# untitled.net
KiCad netlist of a schematic drawn in EAGLE
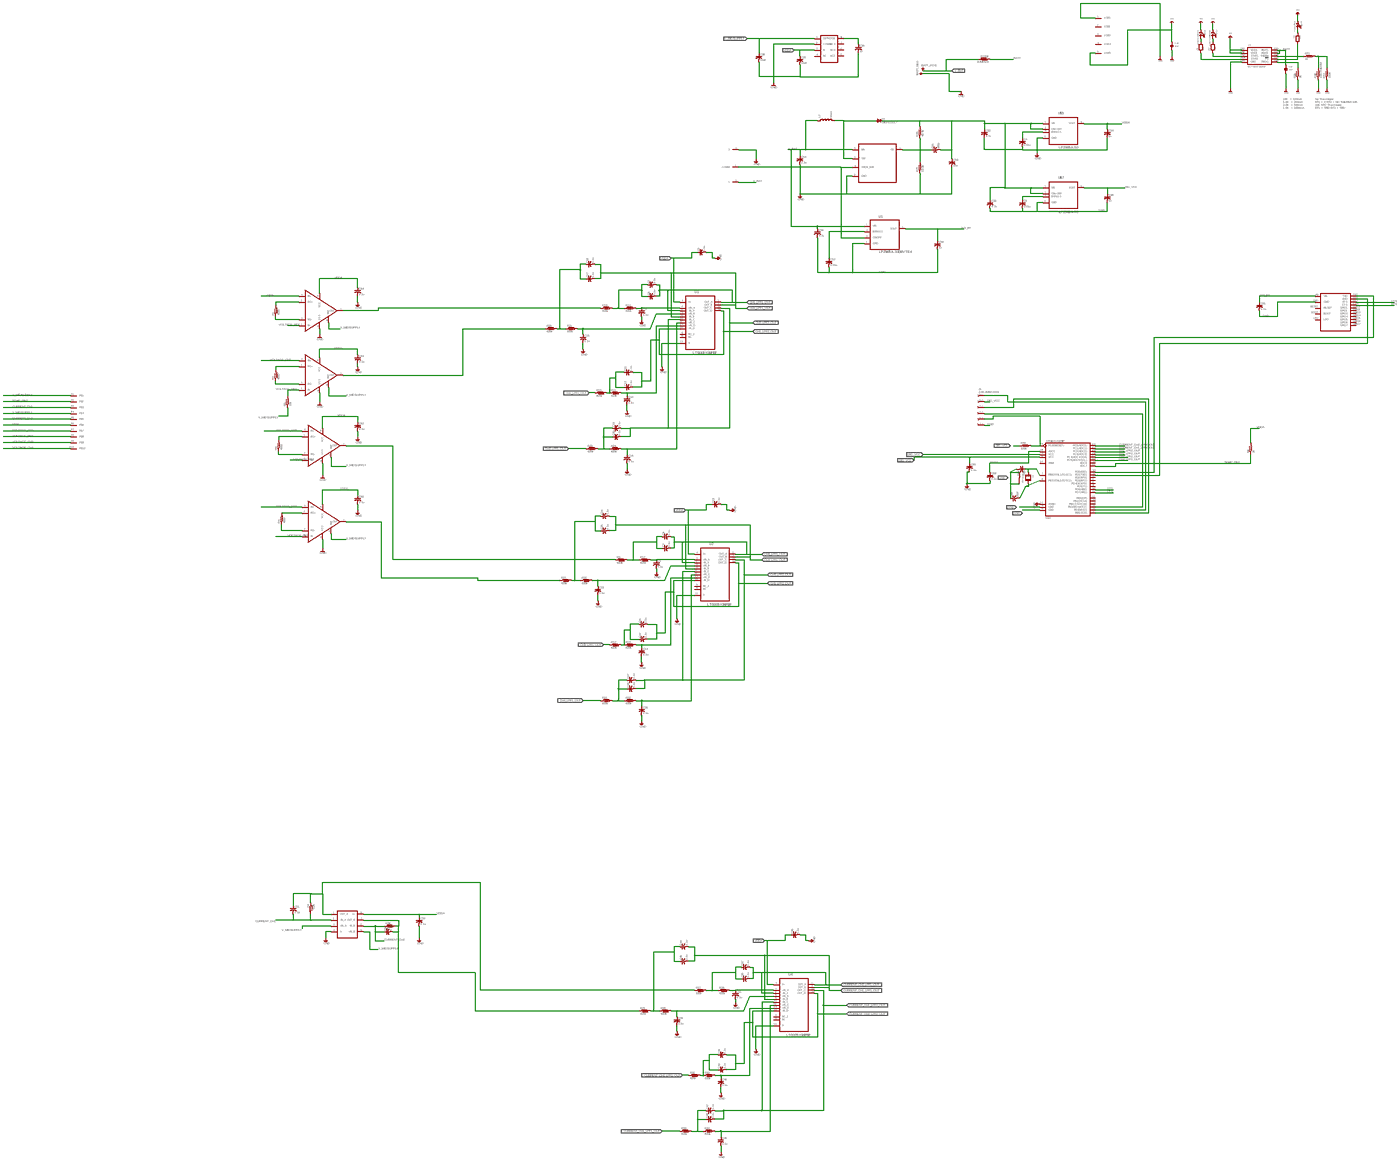
[diagram p0: schematic, sheet 1, overview]
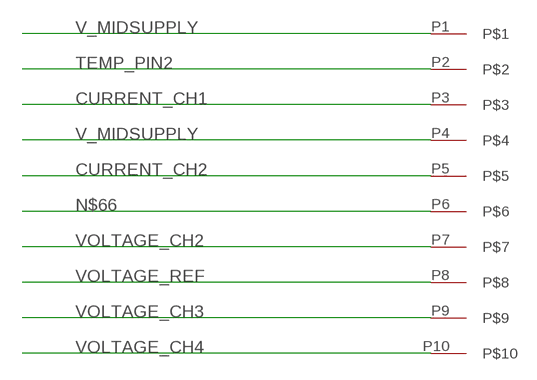
[diagram p1: schematic, sheet 1, part 1 of 7]
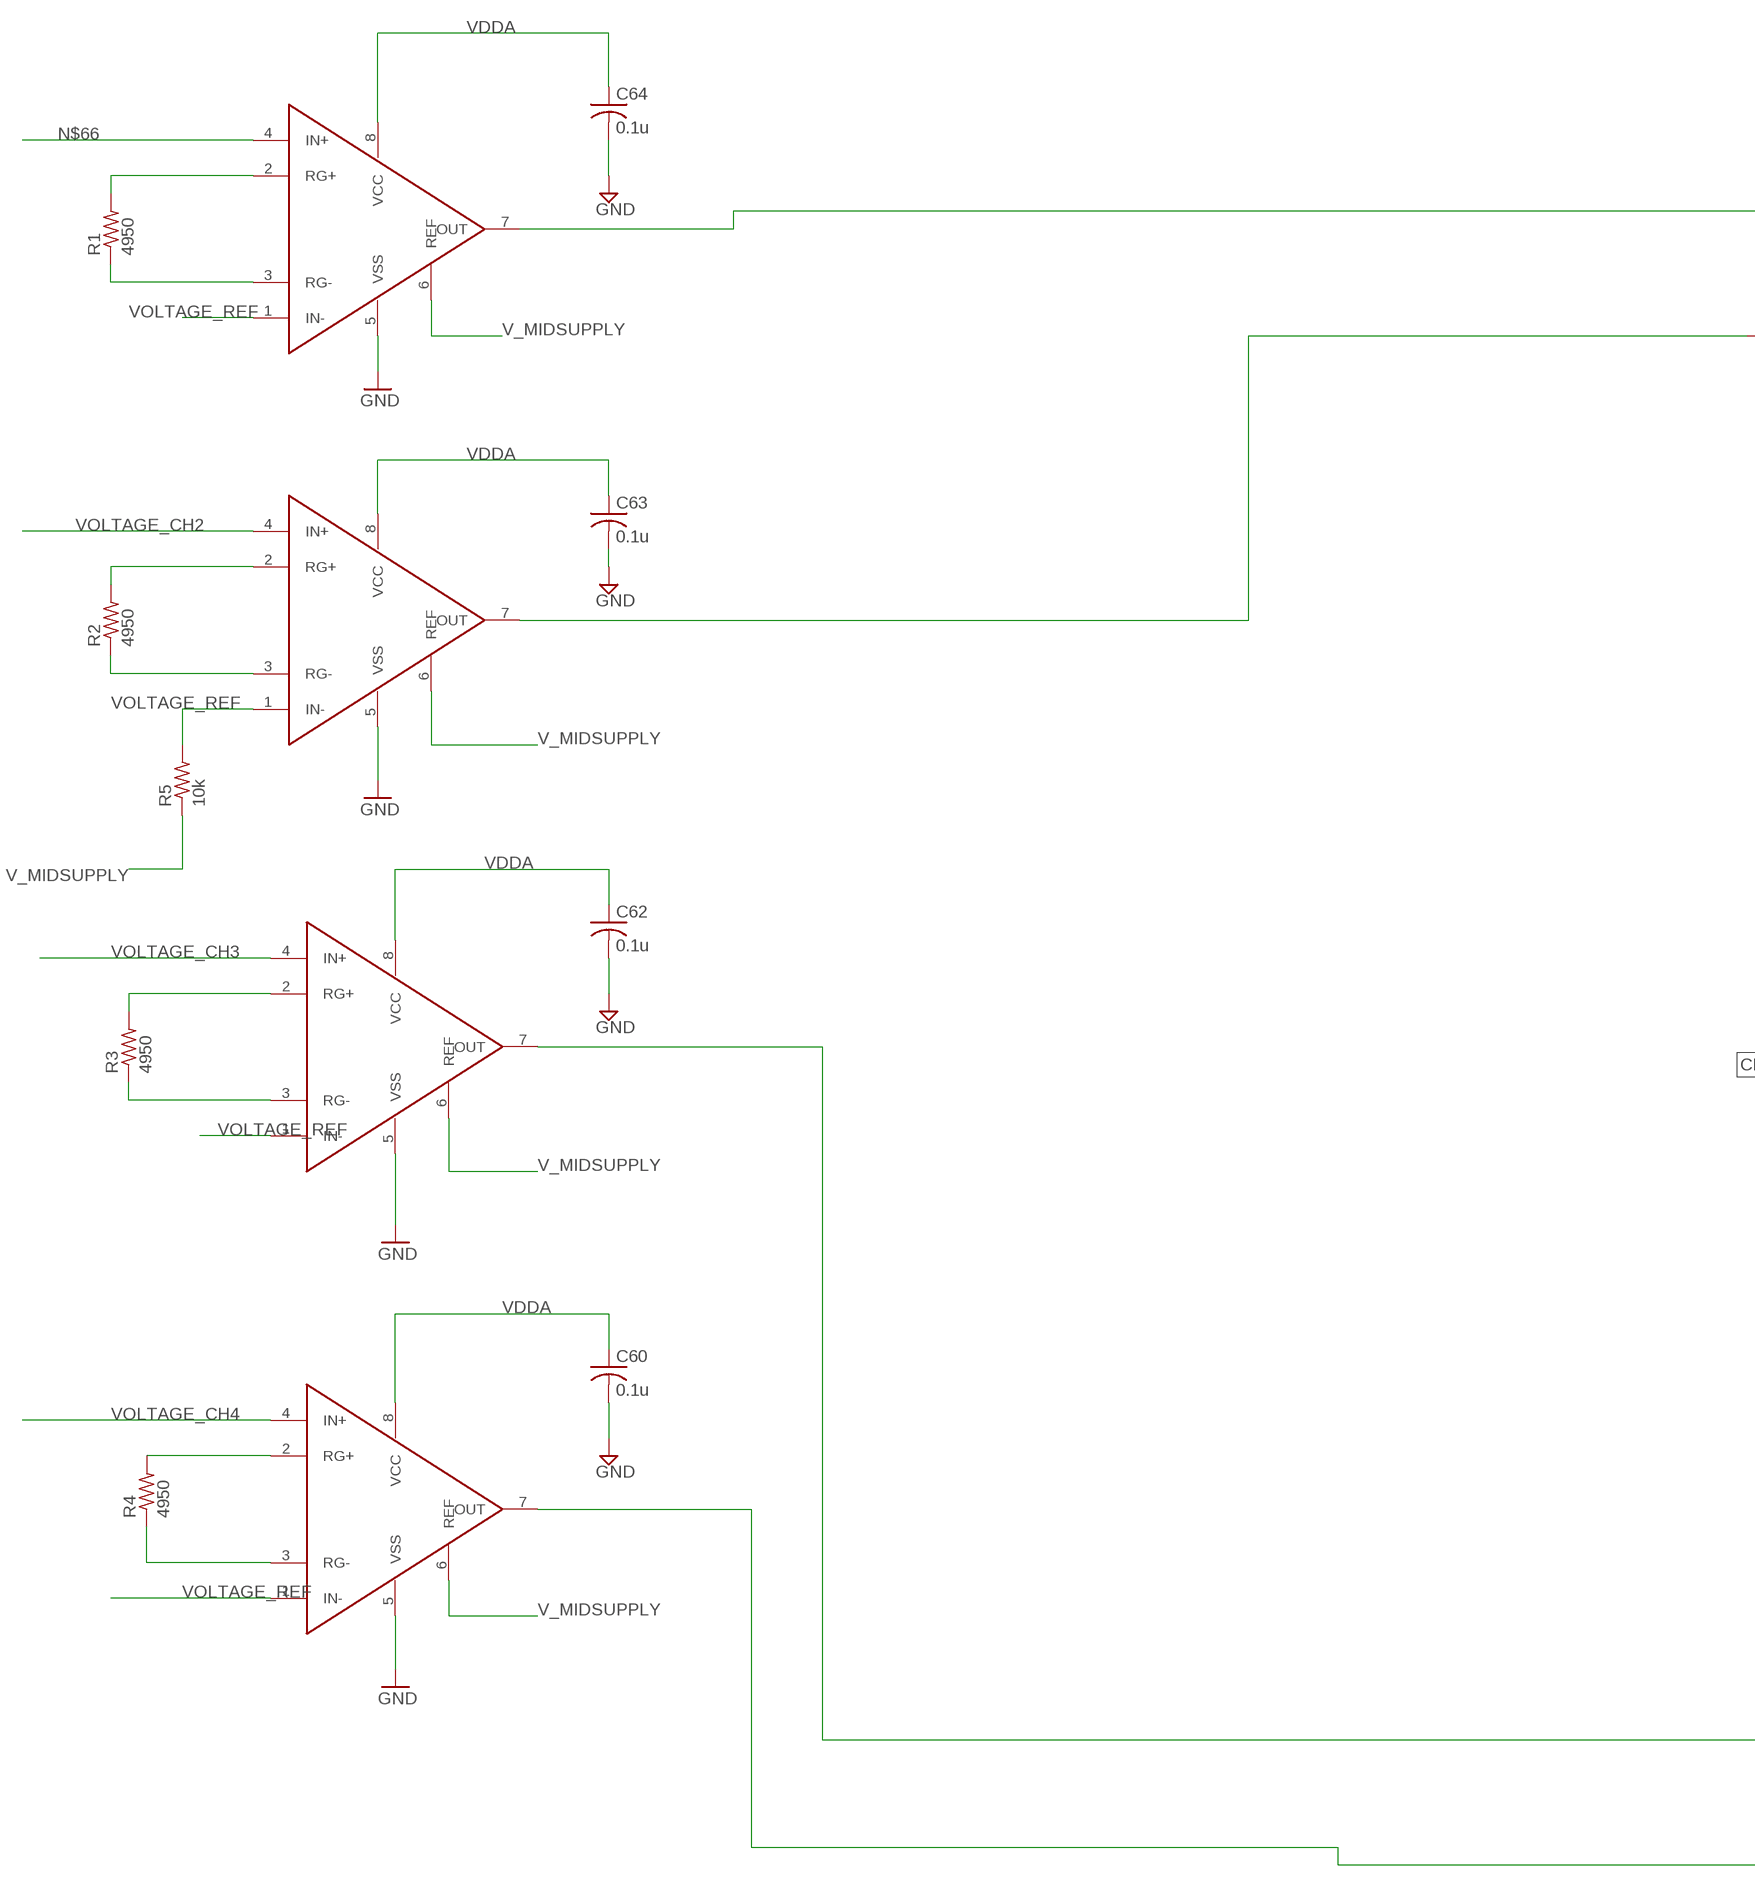
[diagram p2: schematic, sheet 1, part 2 of 7]
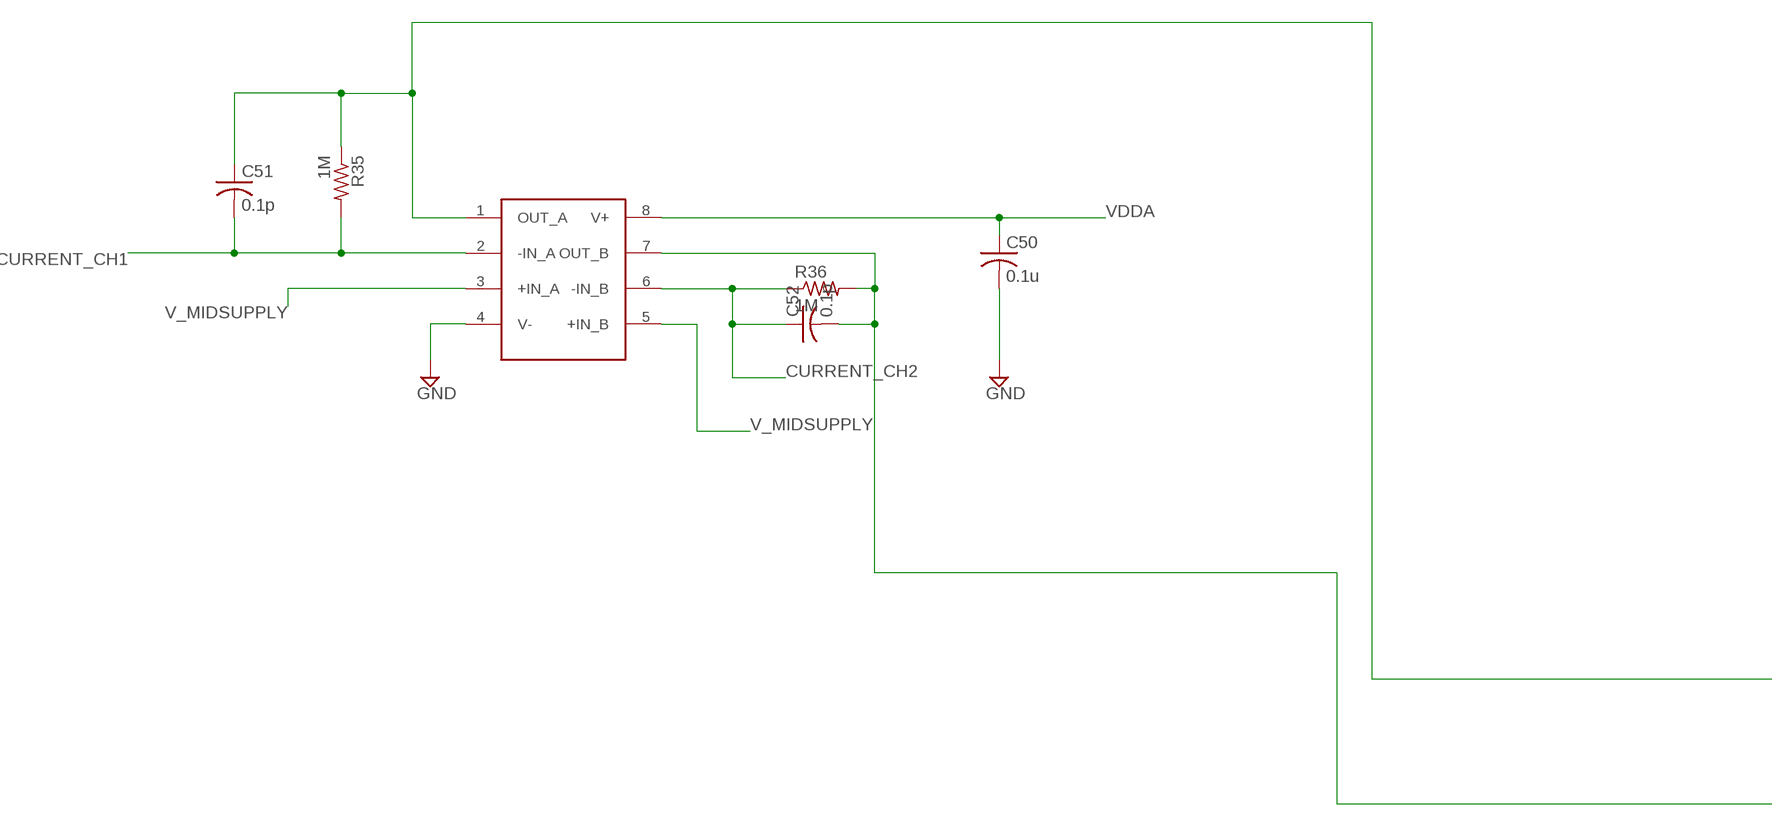
[diagram p3: schematic, sheet 1, part 3 of 7]
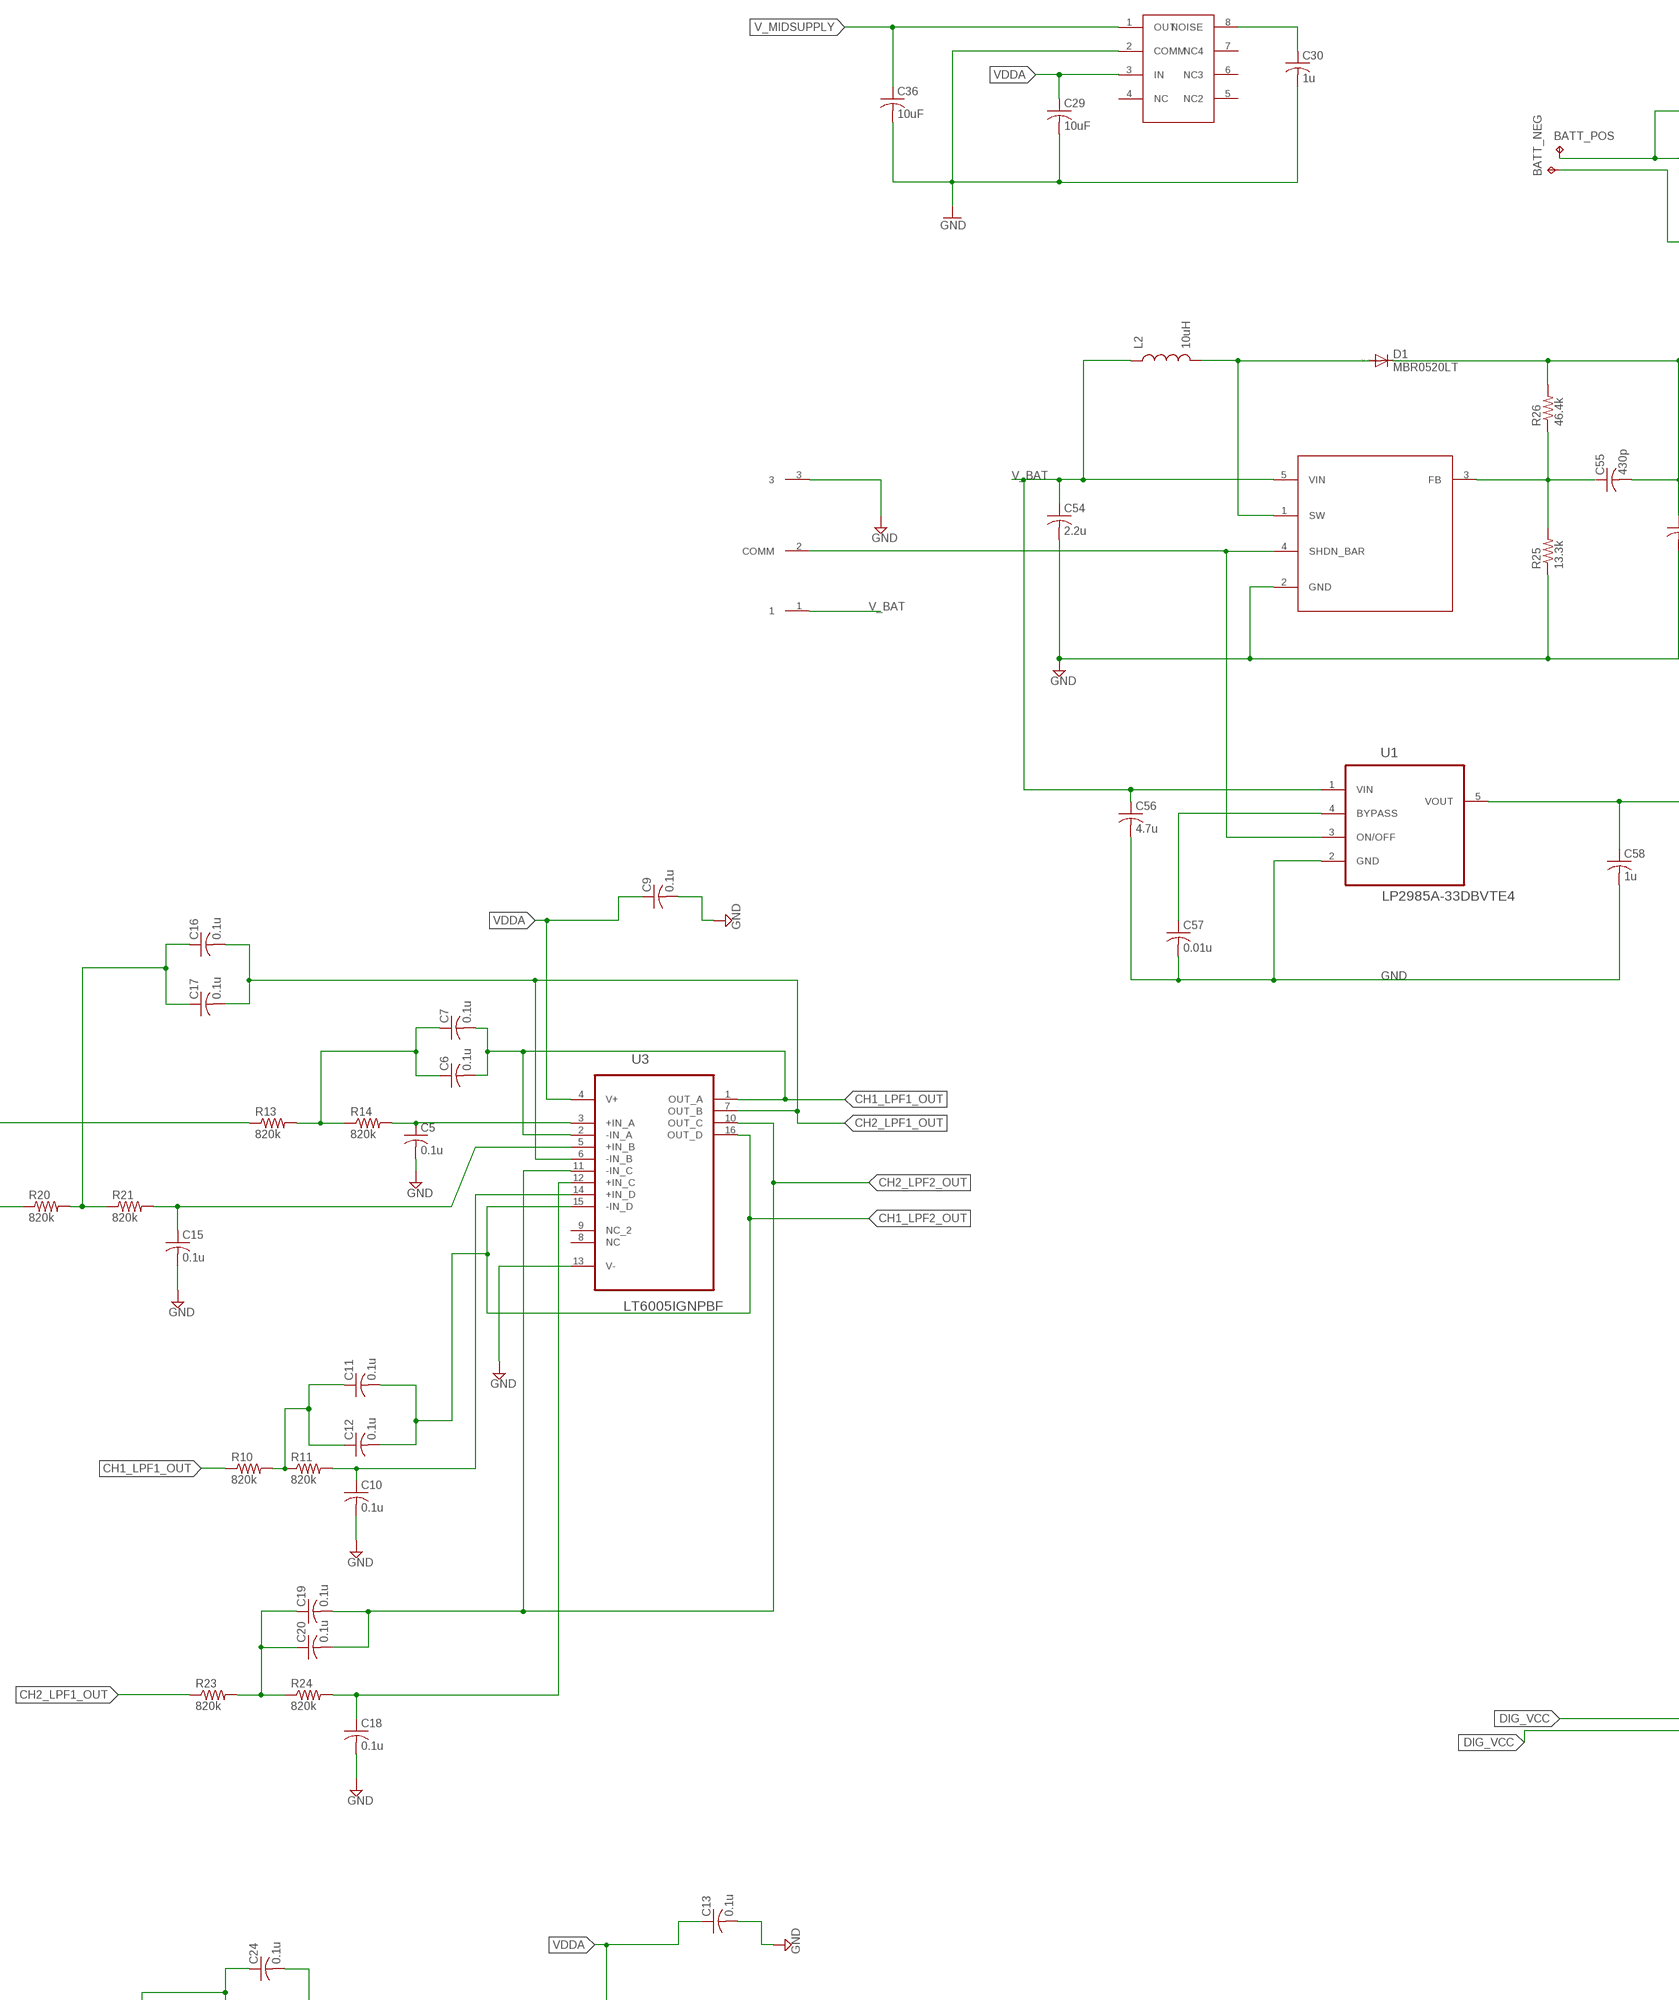
[diagram p4: schematic, sheet 1, part 4 of 7]
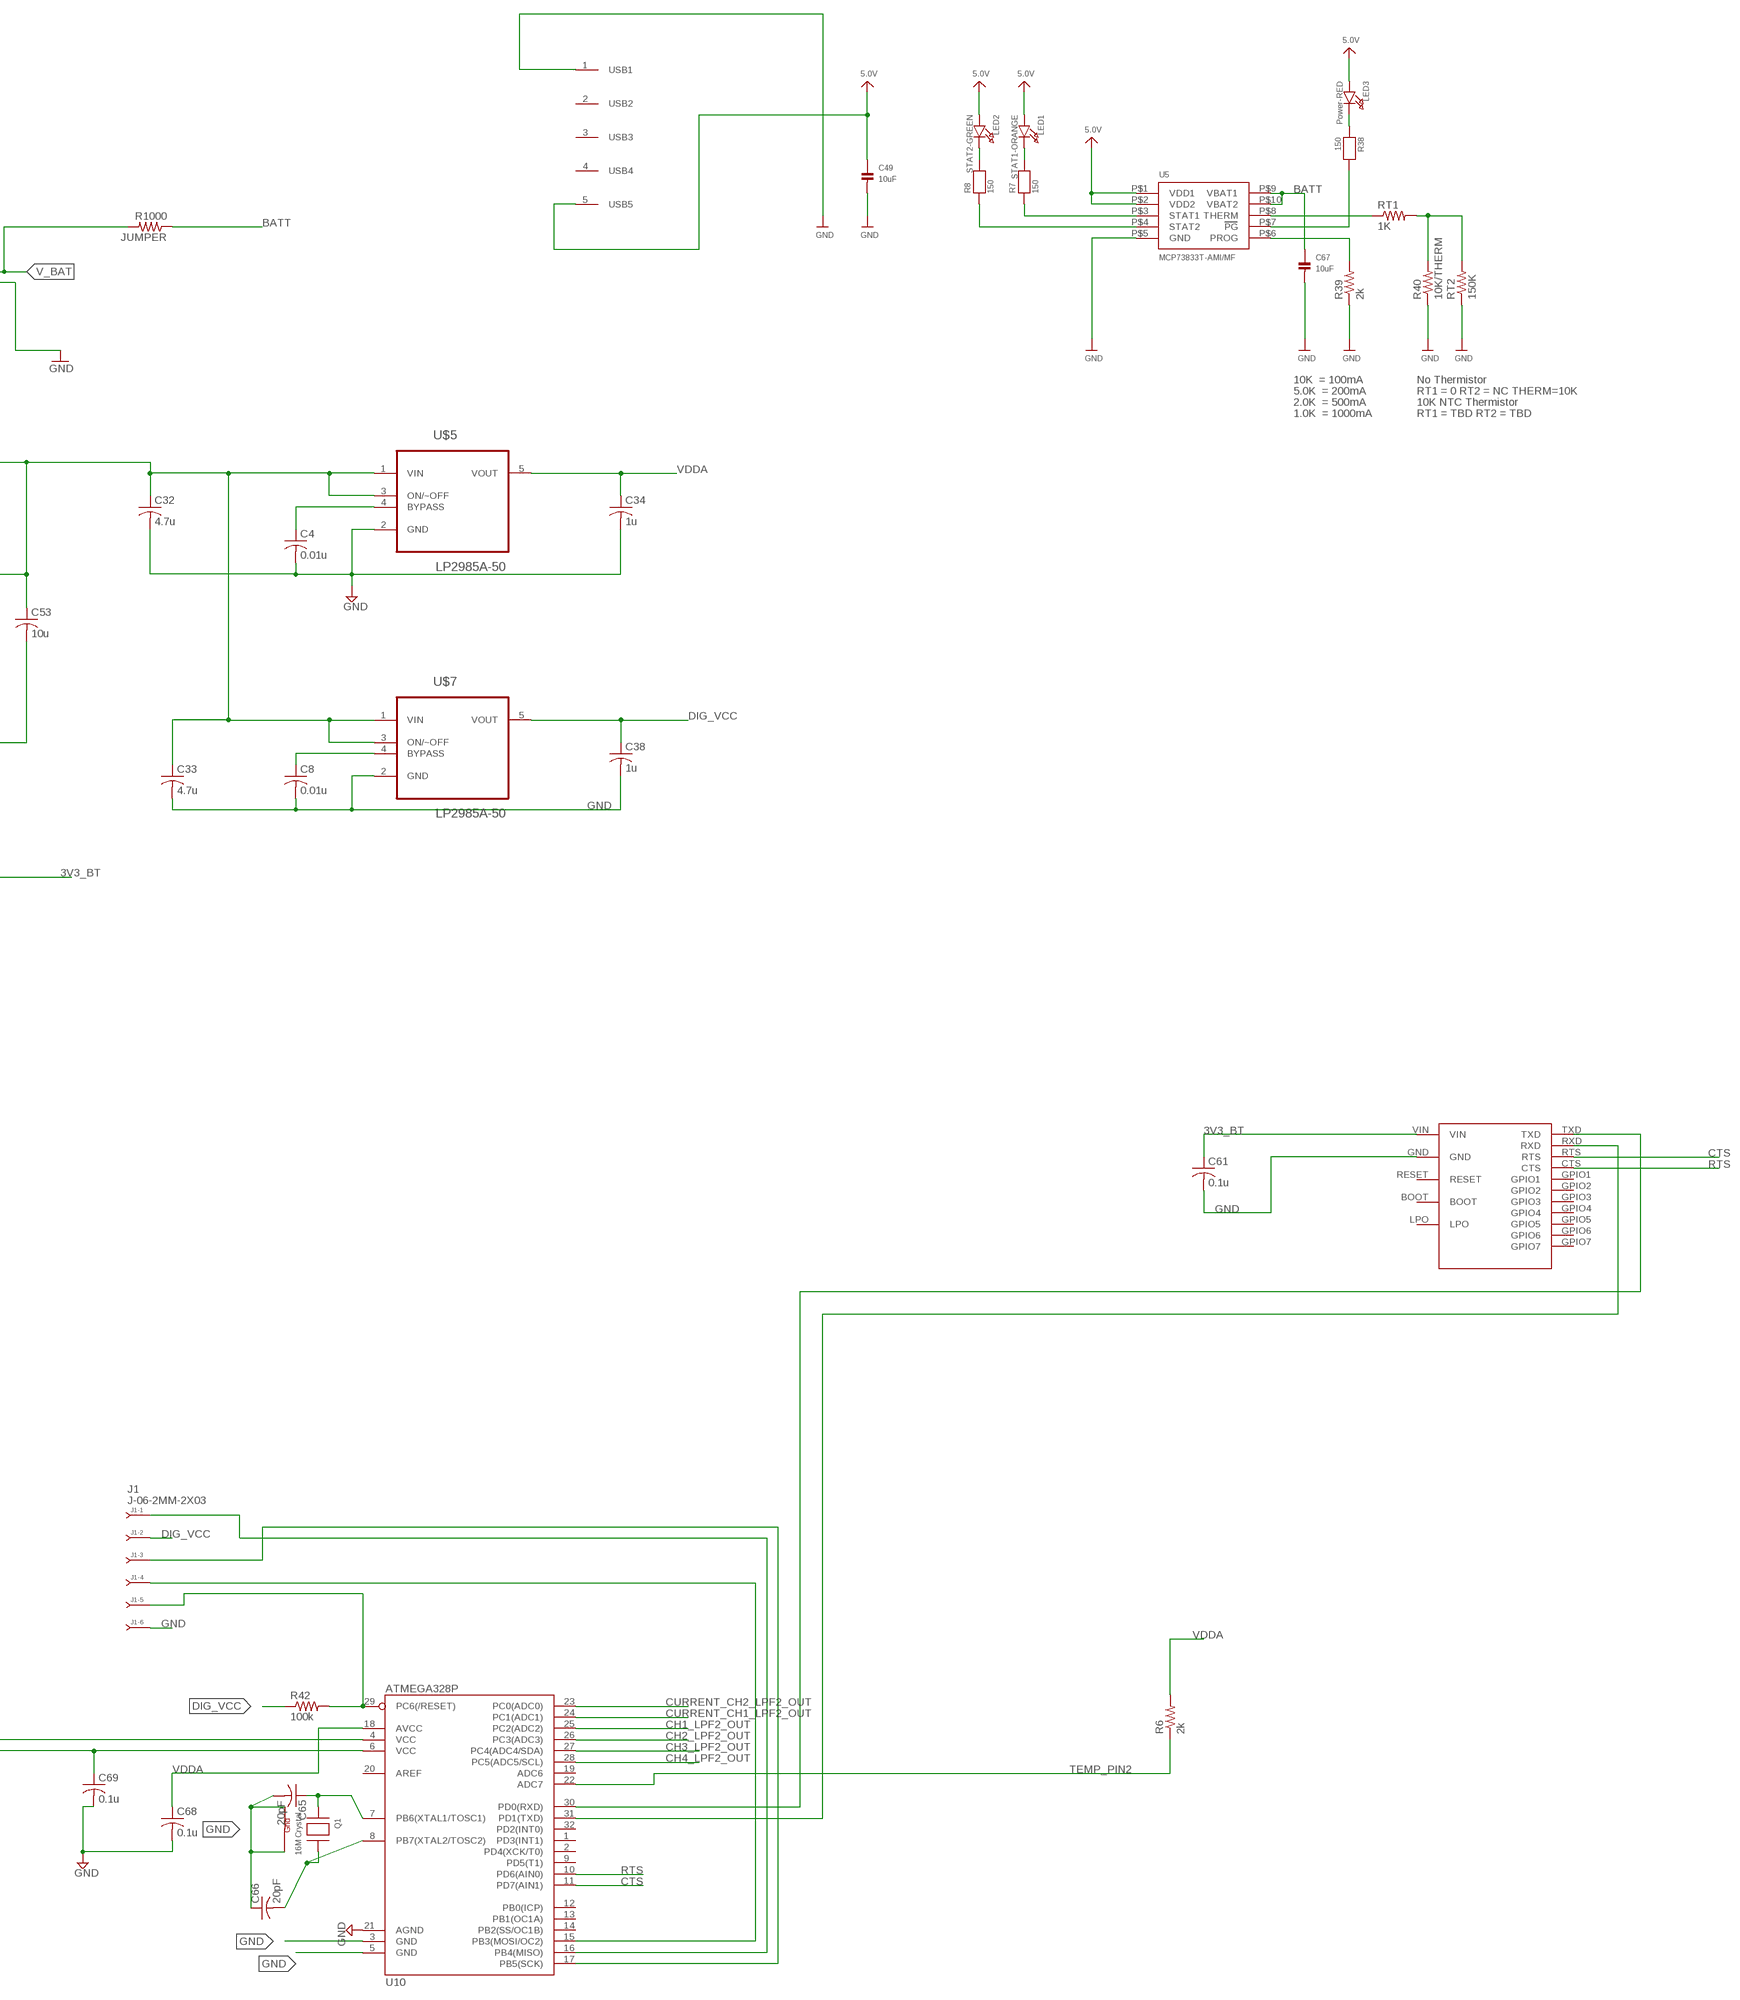
[diagram p5: schematic, sheet 1, part 5 of 7]
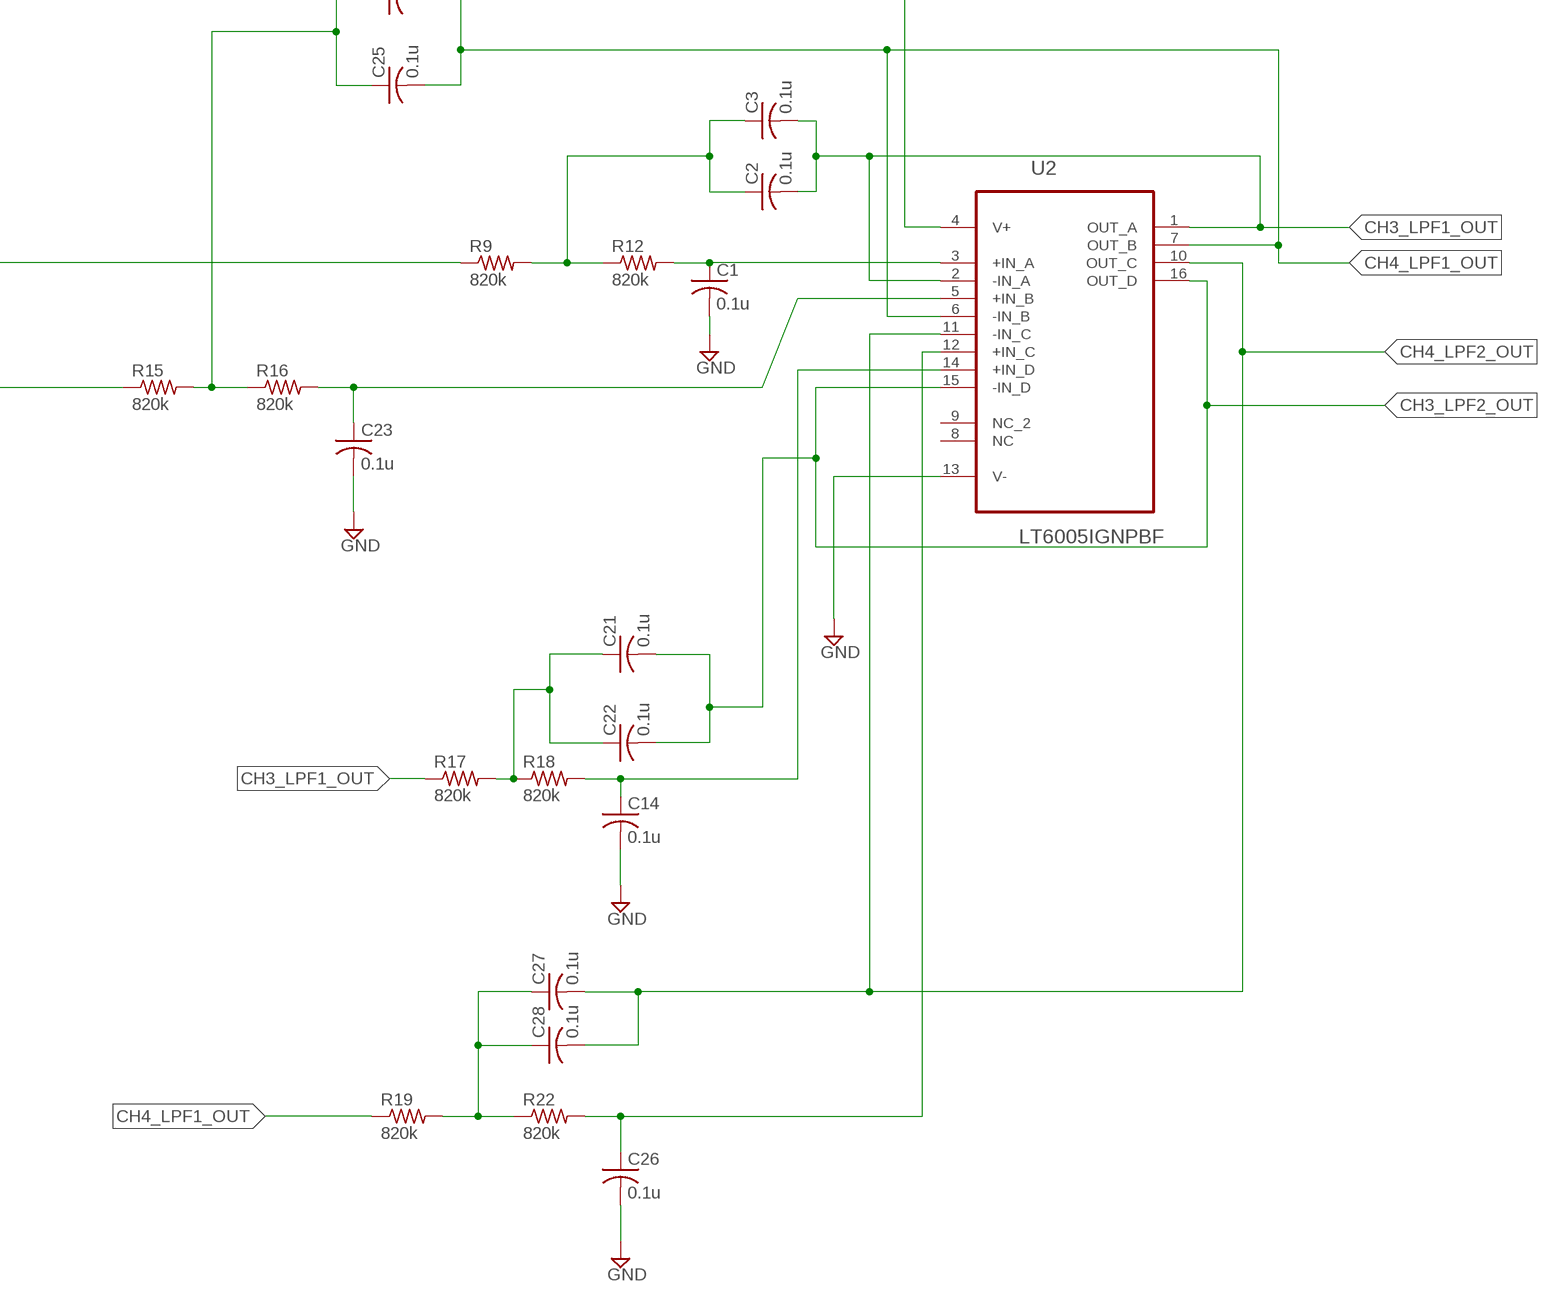
[diagram p6: schematic, sheet 1, part 6 of 7]
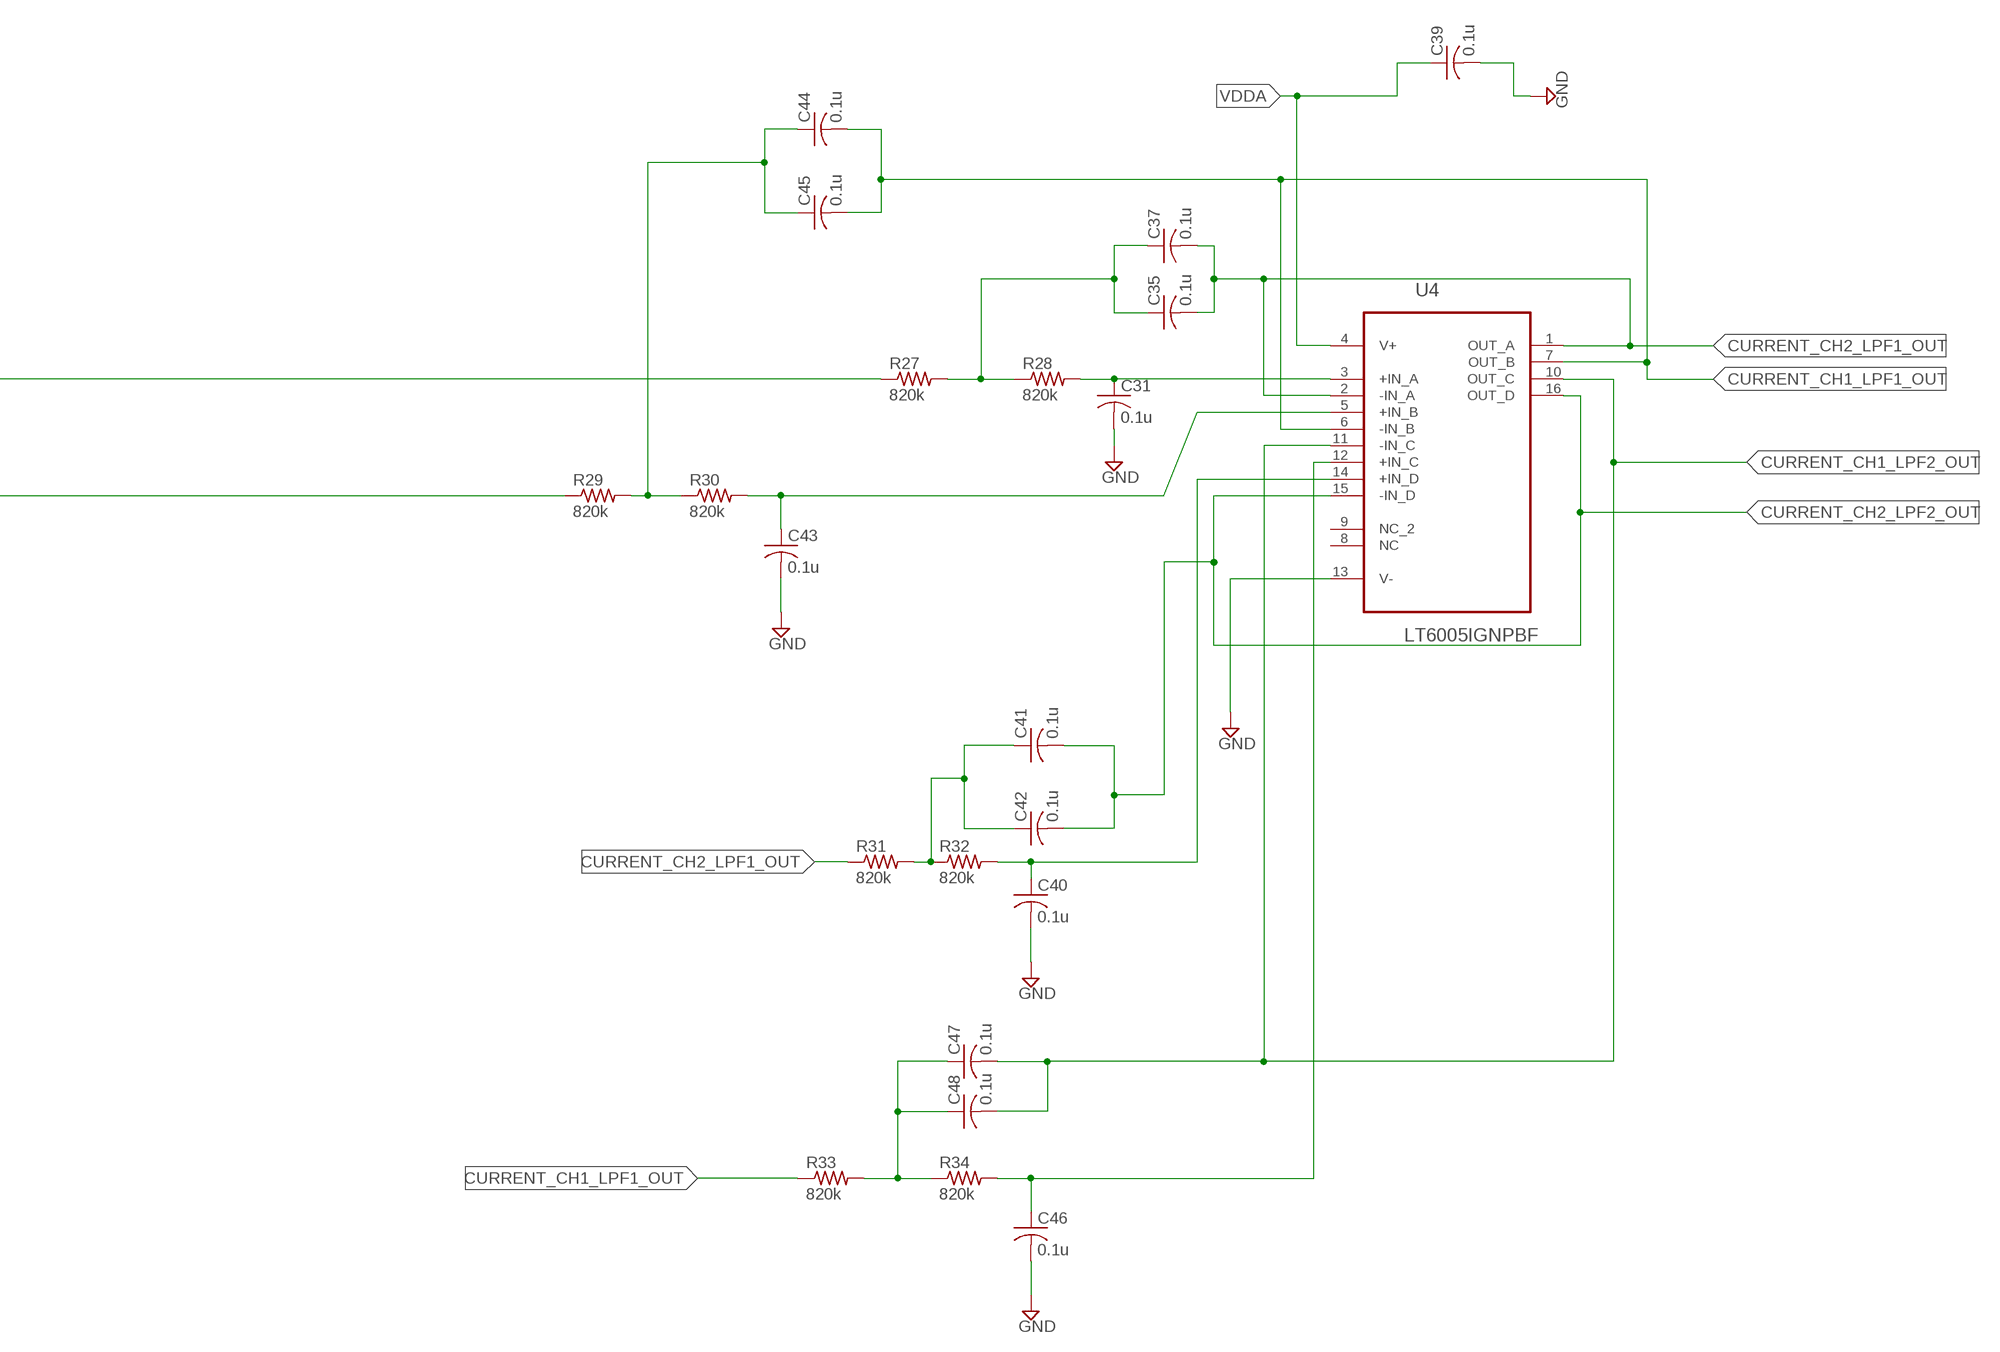
[diagram p7: schematic, sheet 1, part 7 of 7]

(export (version "E")
  (design (tool "Eeschema 10.0.6"))
  (components
    (comp (ref "BATT_NEG")
      (value "TPTP14R")
      (footprint "eagle-import:TP14R")
      (libsource (lib "eagle-import") (part "TPTP14R"))
    )
    (comp (ref "BATT_POS")
      (value "TPTP14R")
      (footprint "eagle-import:TP14R")
      (libsource (lib "eagle-import") (part "TPTP14R"))
    )
    (comp (ref "C1")
      (value "0.1u")
      (footprint "eagle-import:C0201")
      (libsource (lib "eagle-import") (part "C-USC0201"))
    )
    (comp (ref "C2")
      (value "0.1u")
      (footprint "eagle-import:C0201")
      (libsource (lib "eagle-import") (part "C-USC0201"))
    )
    (comp (ref "C3")
      (value "0.1u")
      (footprint "eagle-import:C0201")
      (libsource (lib "eagle-import") (part "C-USC0201"))
    )
    (comp (ref "C4")
      (value "0.01u")
      (footprint "eagle-import:C0402")
      (libsource (lib "eagle-import") (part "resistor_C-USC0402"))
    )
    (comp (ref "C5")
      (value "0.1u")
      (footprint "eagle-import:C0201")
      (libsource (lib "eagle-import") (part "C-USC0201"))
    )
    (comp (ref "C6")
      (value "0.1u")
      (footprint "eagle-import:C0201")
      (libsource (lib "eagle-import") (part "C-USC0201"))
    )
    (comp (ref "C7")
      (value "0.1u")
      (footprint "eagle-import:C0201")
      (libsource (lib "eagle-import") (part "C-USC0201"))
    )
    (comp (ref "C8")
      (value "0.01u")
      (footprint "eagle-import:C0402")
      (libsource (lib "eagle-import") (part "resistor_C-USC0402"))
    )
    (comp (ref "C9")
      (value "0.1u")
      (footprint "eagle-import:C0201")
      (libsource (lib "eagle-import") (part "C-USC0201"))
    )
    (comp (ref "C10")
      (value "0.1u")
      (footprint "eagle-import:C0201")
      (libsource (lib "eagle-import") (part "C-USC0201"))
    )
    (comp (ref "C11")
      (value "0.1u")
      (footprint "eagle-import:C0201")
      (libsource (lib "eagle-import") (part "C-USC0201"))
    )
    (comp (ref "C12")
      (value "0.1u")
      (footprint "eagle-import:C0201")
      (libsource (lib "eagle-import") (part "C-USC0201"))
    )
    (comp (ref "C13")
      (value "0.1u")
      (footprint "eagle-import:C0201")
      (libsource (lib "eagle-import") (part "C-USC0201"))
    )
    (comp (ref "C14")
      (value "0.1u")
      (footprint "eagle-import:C0201")
      (libsource (lib "eagle-import") (part "C-USC0201"))
    )
    (comp (ref "C15")
      (value "0.1u")
      (footprint "eagle-import:C0201")
      (libsource (lib "eagle-import") (part "C-USC0201"))
    )
    (comp (ref "C16")
      (value "0.1u")
      (footprint "eagle-import:C0201")
      (libsource (lib "eagle-import") (part "C-USC0201"))
    )
    (comp (ref "C17")
      (value "0.1u")
      (footprint "eagle-import:C0201")
      (libsource (lib "eagle-import") (part "C-USC0201"))
    )
    (comp (ref "C18")
      (value "0.1u")
      (footprint "eagle-import:C0201")
      (libsource (lib "eagle-import") (part "C-USC0201"))
    )
    (comp (ref "C19")
      (value "0.1u")
      (footprint "eagle-import:C0201")
      (libsource (lib "eagle-import") (part "C-USC0201"))
    )
    (comp (ref "C20")
      (value "0.1u")
      (footprint "eagle-import:C0201")
      (libsource (lib "eagle-import") (part "C-USC0201"))
    )
    (comp (ref "C21")
      (value "0.1u")
      (footprint "eagle-import:C0201")
      (libsource (lib "eagle-import") (part "C-USC0201"))
    )
    (comp (ref "C22")
      (value "0.1u")
      (footprint "eagle-import:C0201")
      (libsource (lib "eagle-import") (part "C-USC0201"))
    )
    (comp (ref "C23")
      (value "0.1u")
      (footprint "eagle-import:C0201")
      (libsource (lib "eagle-import") (part "C-USC0201"))
    )
    (comp (ref "C24")
      (value "0.1u")
      (footprint "eagle-import:C0201")
      (libsource (lib "eagle-import") (part "C-USC0201"))
    )
    (comp (ref "C25")
      (value "0.1u")
      (footprint "eagle-import:C0201")
      (libsource (lib "eagle-import") (part "C-USC0201"))
    )
    (comp (ref "C26")
      (value "0.1u")
      (footprint "eagle-import:C0201")
      (libsource (lib "eagle-import") (part "C-USC0201"))
    )
    (comp (ref "C27")
      (value "0.1u")
      (footprint "eagle-import:C0201")
      (libsource (lib "eagle-import") (part "C-USC0201"))
    )
    (comp (ref "C28")
      (value "0.1u")
      (footprint "eagle-import:C0201")
      (libsource (lib "eagle-import") (part "C-USC0201"))
    )
    (comp (ref "C29")
      (value "10uF")
      (footprint "eagle-import:C0402")
      (libsource (lib "eagle-import") (part "C-USC0402"))
    )
    (comp (ref "C30")
      (value "1u")
      (footprint "eagle-import:C0402")
      (libsource (lib "eagle-import") (part "C-USC0402"))
    )
    (comp (ref "C31")
      (value "0.1u")
      (footprint "eagle-import:C0201")
      (libsource (lib "eagle-import") (part "C-USC0201"))
    )
    (comp (ref "C32")
      (value "4.7u")
      (footprint "eagle-import:C0402")
      (libsource (lib "eagle-import") (part "resistor_C-USC0402"))
    )
    (comp (ref "C33")
      (value "4.7u")
      (footprint "eagle-import:C0402")
      (libsource (lib "eagle-import") (part "resistor_C-USC0402"))
    )
    (comp (ref "C34")
      (value "1u")
      (footprint "eagle-import:C0402")
      (libsource (lib "eagle-import") (part "resistor_C-USC0402"))
    )
    (comp (ref "C35")
      (value "0.1u")
      (footprint "eagle-import:C0201")
      (libsource (lib "eagle-import") (part "C-USC0201"))
    )
    (comp (ref "C36")
      (value "10uF")
      (footprint "eagle-import:C0402")
      (libsource (lib "eagle-import") (part "C-USC0402"))
    )
    (comp (ref "C37")
      (value "0.1u")
      (footprint "eagle-import:C0201")
      (libsource (lib "eagle-import") (part "C-USC0201"))
    )
    (comp (ref "C38")
      (value "1u")
      (footprint "eagle-import:C0402")
      (libsource (lib "eagle-import") (part "resistor_C-USC0402"))
    )
    (comp (ref "C39")
      (value "0.1u")
      (footprint "eagle-import:C0201")
      (libsource (lib "eagle-import") (part "C-USC0201"))
    )
    (comp (ref "C40")
      (value "0.1u")
      (footprint "eagle-import:C0201")
      (libsource (lib "eagle-import") (part "C-USC0201"))
    )
    (comp (ref "C41")
      (value "0.1u")
      (footprint "eagle-import:C0201")
      (libsource (lib "eagle-import") (part "C-USC0201"))
    )
    (comp (ref "C42")
      (value "0.1u")
      (footprint "eagle-import:C0201")
      (libsource (lib "eagle-import") (part "C-USC0201"))
    )
    (comp (ref "C43")
      (value "0.1u")
      (footprint "eagle-import:C0201")
      (libsource (lib "eagle-import") (part "C-USC0201"))
    )
    (comp (ref "C44")
      (value "0.1u")
      (footprint "eagle-import:C0201")
      (libsource (lib "eagle-import") (part "C-USC0201"))
    )
    (comp (ref "C45")
      (value "0.1u")
      (footprint "eagle-import:C0201")
      (libsource (lib "eagle-import") (part "C-USC0201"))
    )
    (comp (ref "C46")
      (value "0.1u")
      (footprint "eagle-import:C0201")
      (libsource (lib "eagle-import") (part "C-USC0201"))
    )
    (comp (ref "C47")
      (value "0.1u")
      (footprint "eagle-import:C0201")
      (libsource (lib "eagle-import") (part "C-USC0201"))
    )
    (comp (ref "C48")
      (value "0.1u")
      (footprint "eagle-import:C0201")
      (libsource (lib "eagle-import") (part "C-USC0201"))
    )
    (comp (ref "C49")
      (value "10uF")
      (footprint "eagle-import:0402")
      (libsource (lib "eagle-import") (part "CAP_CERAMIC0402"))
    )
    (comp (ref "C50")
      (value "0.1u")
      (footprint "eagle-import:C0201")
      (libsource (lib "eagle-import") (part "C-USC0201"))
    )
    (comp (ref "C51")
      (value "0.1p")
      (footprint "eagle-import:C0201")
      (libsource (lib "eagle-import") (part "C-USC0201"))
    )
    (comp (ref "C52")
      (value "0.1p")
      (footprint "eagle-import:C0201")
      (libsource (lib "eagle-import") (part "C-USC0201"))
    )
    (comp (ref "C53")
      (value "10u")
      (footprint "eagle-import:C0402")
      (libsource (lib "eagle-import") (part "resistor_C-USC0402"))
    )
    (comp (ref "C54")
      (value "2.2u")
      (footprint "eagle-import:C0402")
      (libsource (lib "eagle-import") (part "resistor_C-USC0402"))
    )
    (comp (ref "C55")
      (value "430p")
      (footprint "eagle-import:C0402")
      (libsource (lib "eagle-import") (part "resistor_C-USC0402"))
    )
    (comp (ref "C56")
      (value "4.7u")
      (footprint "eagle-import:C0402")
      (libsource (lib "eagle-import") (part "resistor_C-USC0402"))
    )
    (comp (ref "C57")
      (value "0.01u")
      (footprint "eagle-import:C0402")
      (libsource (lib "eagle-import") (part "resistor_C-USC0402"))
    )
    (comp (ref "C58")
      (value "1u")
      (footprint "eagle-import:C0402")
      (libsource (lib "eagle-import") (part "resistor_C-USC0402"))
    )
    (comp (ref "C60")
      (value "0.1u")
      (footprint "eagle-import:C0201")
      (libsource (lib "eagle-import") (part "C-USC0201"))
    )
    (comp (ref "C61")
      (value "0.1u")
      (footprint "eagle-import:C0402")
      (libsource (lib "eagle-import") (part "resistor_C-USC0402"))
    )
    (comp (ref "C62")
      (value "0.1u")
      (footprint "eagle-import:C0201")
      (libsource (lib "eagle-import") (part "C-USC0201"))
    )
    (comp (ref "C63")
      (value "0.1u")
      (footprint "eagle-import:C0201")
      (libsource (lib "eagle-import") (part "C-USC0201"))
    )
    (comp (ref "C64")
      (value "0.1u")
      (footprint "eagle-import:C0201")
      (libsource (lib "eagle-import") (part "C-USC0201"))
    )
    (comp (ref "C65")
      (value "20pF")
      (footprint "eagle-import:C0402")
      (libsource (lib "eagle-import") (part "C-USC0402"))
    )
    (comp (ref "C66")
      (value "20pF")
      (footprint "eagle-import:C0402")
      (libsource (lib "eagle-import") (part "C-USC0402"))
    )
    (comp (ref "C67")
      (value "10uF")
      (footprint "eagle-import:0402")
      (libsource (lib "eagle-import") (part "CAP_CERAMIC0402"))
    )
    (comp (ref "C68")
      (value "0.1u")
      (footprint "eagle-import:C0201")
      (libsource (lib "eagle-import") (part "C-USC0201"))
    )
    (comp (ref "C69")
      (value "0.1u")
      (footprint "eagle-import:C0201")
      (libsource (lib "eagle-import") (part "C-USC0201"))
    )
    (comp (ref "D1")
      (value "MBR0520LT")
      (footprint "eagle-import:SOD123")
      (libsource (lib "eagle-import") (part "MBR0520LT"))
    )
    (comp (ref "J1")
      (value "J-06-2MM-2X03")
      (footprint "eagle-import:DIL-2MM-2X03")
      (libsource (lib "eagle-import") (part "J-06-2MM-2X03"))
    )
    (comp (ref "JUMPER")
      (value "R1000")
      (footprint "eagle-import:R0402")
      (libsource (lib "eagle-import") (part "resistor_R-US_R0402"))
    )
    (comp (ref "L2")
      (value "10uH")
      (footprint "eagle-import:0805")
      (libsource (lib "eagle-import") (part "INDUCTOR0805"))
    )
    (comp (ref "LED1")
      (value "STAT1-ORANGE")
      (footprint "eagle-import:CHIPLED_0805")
      (libsource (lib "eagle-import") (part "LED0805"))
    )
    (comp (ref "LED2")
      (value "STAT2-GREEN")
      (footprint "eagle-import:CHIPLED_0805")
      (libsource (lib "eagle-import") (part "LED0805"))
    )
    (comp (ref "LED3")
      (value "Power-RED")
      (footprint "eagle-import:CHIPLED_0805")
      (libsource (lib "eagle-import") (part "LED0805"))
    )
    (comp (ref "Q1")
      (value "16M Crystal")
      (footprint "eagle-import:NX3225")
      (libsource (lib "eagle-import") (part "XTAL-4-3225"))
    )
    (comp (ref "R1")
      (value "4950")
      (footprint "eagle-import:R0201")
      (libsource (lib "eagle-import") (part "R-US_R0201"))
    )
    (comp (ref "R2")
      (value "4950")
      (footprint "eagle-import:R0201")
      (libsource (lib "eagle-import") (part "R-US_R0201"))
    )
    (comp (ref "R3")
      (value "4950")
      (footprint "eagle-import:R0201")
      (libsource (lib "eagle-import") (part "R-US_R0201"))
    )
    (comp (ref "R4")
      (value "4950")
      (footprint "eagle-import:R0201")
      (libsource (lib "eagle-import") (part "R-US_R0201"))
    )
    (comp (ref "R5")
      (value "10k")
      (footprint "eagle-import:R0402")
      (libsource (lib "eagle-import") (part "resistor_R-US_R0402"))
    )
    (comp (ref "R6")
      (value "2k")
      (footprint "eagle-import:R0402")
      (libsource (lib "eagle-import") (part "resistor_R-US_R0402"))
    )
    (comp (ref "R7")
      (value "150")
      (footprint "eagle-import:0402")
      (libsource (lib "eagle-import") (part "RESISTOR0402"))
    )
    (comp (ref "R8")
      (value "150")
      (footprint "eagle-import:0402")
      (libsource (lib "eagle-import") (part "RESISTOR0402"))
    )
    (comp (ref "R9")
      (value "820k")
      (footprint "eagle-import:R0201")
      (libsource (lib "eagle-import") (part "R-US_R0201"))
    )
    (comp (ref "R10")
      (value "820k")
      (footprint "eagle-import:R0201")
      (libsource (lib "eagle-import") (part "R-US_R0201"))
    )
    (comp (ref "R11")
      (value "820k")
      (footprint "eagle-import:R0201")
      (libsource (lib "eagle-import") (part "R-US_R0201"))
    )
    (comp (ref "R12")
      (value "820k")
      (footprint "eagle-import:R0201")
      (libsource (lib "eagle-import") (part "R-US_R0201"))
    )
    (comp (ref "R13")
      (value "820k")
      (footprint "eagle-import:R0201")
      (libsource (lib "eagle-import") (part "R-US_R0201"))
    )
    (comp (ref "R14")
      (value "820k")
      (footprint "eagle-import:R0201")
      (libsource (lib "eagle-import") (part "R-US_R0201"))
    )
    (comp (ref "R15")
      (value "820k")
      (footprint "eagle-import:R0201")
      (libsource (lib "eagle-import") (part "R-US_R0201"))
    )
    (comp (ref "R16")
      (value "820k")
      (footprint "eagle-import:R0201")
      (libsource (lib "eagle-import") (part "R-US_R0201"))
    )
    (comp (ref "R17")
      (value "820k")
      (footprint "eagle-import:R0201")
      (libsource (lib "eagle-import") (part "R-US_R0201"))
    )
    (comp (ref "R18")
      (value "820k")
      (footprint "eagle-import:R0201")
      (libsource (lib "eagle-import") (part "R-US_R0201"))
    )
    (comp (ref "R19")
      (value "820k")
      (footprint "eagle-import:R0201")
      (libsource (lib "eagle-import") (part "R-US_R0201"))
    )
    (comp (ref "R20")
      (value "820k")
      (footprint "eagle-import:R0201")
      (libsource (lib "eagle-import") (part "R-US_R0201"))
    )
    (comp (ref "R21")
      (value "820k")
      (footprint "eagle-import:R0201")
      (libsource (lib "eagle-import") (part "R-US_R0201"))
    )
    (comp (ref "R22")
      (value "820k")
      (footprint "eagle-import:R0201")
      (libsource (lib "eagle-import") (part "R-US_R0201"))
    )
    (comp (ref "R23")
      (value "820k")
      (footprint "eagle-import:R0201")
      (libsource (lib "eagle-import") (part "R-US_R0201"))
    )
    (comp (ref "R24")
      (value "820k")
      (footprint "eagle-import:R0201")
      (libsource (lib "eagle-import") (part "R-US_R0201"))
    )
    (comp (ref "R25")
      (value "13.3k")
      (footprint "eagle-import:R0402")
      (libsource (lib "eagle-import") (part "resistor_R-US_R0402"))
    )
    (comp (ref "R26")
      (value "46.4k")
      (footprint "eagle-import:R0402")
      (libsource (lib "eagle-import") (part "resistor_R-US_R0402"))
    )
    (comp (ref "R27")
      (value "820k")
      (footprint "eagle-import:R0201")
      (libsource (lib "eagle-import") (part "R-US_R0201"))
    )
    (comp (ref "R28")
      (value "820k")
      (footprint "eagle-import:R0201")
      (libsource (lib "eagle-import") (part "R-US_R0201"))
    )
    (comp (ref "R29")
      (value "820k")
      (footprint "eagle-import:R0201")
      (libsource (lib "eagle-import") (part "R-US_R0201"))
    )
    (comp (ref "R30")
      (value "820k")
      (footprint "eagle-import:R0201")
      (libsource (lib "eagle-import") (part "R-US_R0201"))
    )
    (comp (ref "R31")
      (value "820k")
      (footprint "eagle-import:R0201")
      (libsource (lib "eagle-import") (part "R-US_R0201"))
    )
    (comp (ref "R32")
      (value "820k")
      (footprint "eagle-import:R0201")
      (libsource (lib "eagle-import") (part "R-US_R0201"))
    )
    (comp (ref "R33")
      (value "820k")
      (footprint "eagle-import:R0201")
      (libsource (lib "eagle-import") (part "R-US_R0201"))
    )
    (comp (ref "R34")
      (value "820k")
      (footprint "eagle-import:R0201")
      (libsource (lib "eagle-import") (part "R-US_R0201"))
    )
    (comp (ref "R35")
      (value "1M")
      (footprint "eagle-import:R0201")
      (libsource (lib "eagle-import") (part "R-US_R0201"))
    )
    (comp (ref "R36")
      (value "1M")
      (footprint "eagle-import:R0201")
      (libsource (lib "eagle-import") (part "R-US_R0201"))
    )
    (comp (ref "R38")
      (value "150")
      (footprint "eagle-import:0402")
      (libsource (lib "eagle-import") (part "RESISTOR0402"))
    )
    (comp (ref "R39")
      (value "2k")
      (footprint "eagle-import:R0402")
      (libsource (lib "eagle-import") (part "R-US_R0402"))
    )
    (comp (ref "R40")
      (value "10K/THERM")
      (footprint "eagle-import:R0402")
      (libsource (lib "eagle-import") (part "R-US_R0402"))
    )
    (comp (ref "R42")
      (value "100k")
      (footprint "eagle-import:R0201")
      (libsource (lib "eagle-import") (part "R-US_R0201"))
    )
    (comp (ref "RT1")
      (value "1K")
      (footprint "eagle-import:R0402")
      (libsource (lib "eagle-import") (part "R-US_R0402"))
    )
    (comp (ref "RT2")
      (value "150K")
      (footprint "eagle-import:R0402")
      (libsource (lib "eagle-import") (part "R-US_R0402"))
    )
    (comp (ref "U$1")
      (value "SOIC8_INAMPMSOP")
      (footprint "eagle-import:MSOP08")
      (libsource (lib "eagle-import") (part "SOIC8_INAMPMSOP"))
    )
    (comp (ref "U$2")
      (value "SOIC8_INAMPMSOP")
      (footprint "eagle-import:MSOP08")
      (libsource (lib "eagle-import") (part "SOIC8_INAMPMSOP"))
    )
    (comp (ref "U$3")
      (value "SOIC8_INAMPMSOP")
      (footprint "eagle-import:MSOP08")
      (libsource (lib "eagle-import") (part "SOIC8_INAMPMSOP"))
    )
    (comp (ref "U$4")
      (value "SOIC8_INAMPMSOP")
      (footprint "eagle-import:MSOP08")
      (libsource (lib "eagle-import") (part "SOIC8_INAMPMSOP"))
    )
    (comp (ref "U$5")
      (value "LP2985A-50")
      (footprint "eagle-import:SOT95P280X145-5N")
      (libsource (lib "eagle-import") (part "LP2985A-50"))
    )
    (comp (ref "U$6")
      (value "AD8462")
      (footprint "eagle-import:MSOP08")
      (libsource (lib "eagle-import") (part "AD8462"))
    )
    (comp (ref "U$7")
      (value "LP2985A-50")
      (footprint "eagle-import:SOT95P280X145-5N")
      (libsource (lib "eagle-import") (part "LP2985A-50"))
    )
    (comp (ref "U$8")
      (value "SPBT2632C2A")
      (footprint "eagle-import:SPBT2632C2A")
      (libsource (lib "eagle-import") (part "SPBT2632C2A"))
    )
    (comp (ref "U$9")
      (value "LM27313")
      (footprint "eagle-import:SOT95P280X145-5N")
      (libsource (lib "eagle-import") (part "LM27313"))
    )
    (comp (ref "U$10")
      (value "MINI-USB-10033526-N3212LF")
      (footprint "eagle-import:MINI-USB-10033526-N3212LF")
      (libsource (lib "eagle-import") (part "MINI-USB-10033526-N3212LF"))
    )
    (comp (ref "U$11")
      (value "JS102011SAQN")
      (footprint "eagle-import:JS102011SAQN")
      (libsource (lib "eagle-import") (part "JS102011SAQN"))
    )
    (comp (ref "U$12")
      (value "5-104074-1-CONNECTOR")
      (footprint "eagle-import:5-104074-1-CONNECTOR")
      (libsource (lib "eagle-import") (part "5-104074-1-CONNECTOR"))
    )
    (comp (ref "U1")
      (value "LP2985A-33DBVTE4")
      (footprint "eagle-import:SOT95P280X145-5N")
      (libsource (lib "eagle-import") (part "LP2985A-33DBVTE4"))
    )
    (comp (ref "U2")
      (value "LT6005IGNPBF")
      (footprint "eagle-import:SOP63P600X175-16N")
      (fields (field (name "MPN") "LT6005IGN#PBF"))
      (libsource (lib "eagle-import") (part "LT6005IGNPBF"))
    )
    (comp (ref "U3")
      (value "LT6005IGNPBF")
      (footprint "eagle-import:SOP63P600X175-16N")
      (fields (field (name "MPN") "LT6005IGN#PBF"))
      (libsource (lib "eagle-import") (part "LT6005IGNPBF"))
    )
    (comp (ref "U4")
      (value "LT6005IGNPBF")
      (footprint "eagle-import:SOP63P600X175-16N")
      (fields (field (name "MPN") "LT6005IGN#PBF"))
      (libsource (lib "eagle-import") (part "LT6005IGNPBF"))
    )
    (comp (ref "U5")
      (value "MCP73833T-AMI/MF")
      (footprint "eagle-import:DFN10_3X3MM")
      (libsource (lib "eagle-import") (part "MCP73833DFN"))
    )
    (comp (ref "U10")
      (value "ATMEGA328P")
      (footprint "eagle-import:TQFP32-08")
      (libsource (lib "eagle-import") (part "ATMEGA328_SMT"))
    )
    (comp (ref "U15")
      (value "TLE2426IDR")
      (footprint "eagle-import:R_8")
      (libsource (lib "eagle-import") (part "TLE2426IDR"))
    )
  )
  (nets
    (net (code "1") (name "/3V3_BT") (class "Default")
      (node (ref "C58") (pin "1") (pinfunction "1_1") (pintype "passive"))
      (node (ref "C61") (pin "1") (pinfunction "1_1") (pintype "passive"))
      (node (ref "U$8") (pin "VIN") (pinfunction "VIN_VIN") (pintype "bidirectional"))
      (node (ref "U1") (pin "5") (pinfunction "VOUT_5") (pintype "output"))
    )
    (net (code "2") (name "/BATT") (class "Default")
      (node (ref "C67") (pin "1") (pinfunction "P$1_1") (pintype "passive"))
      (node (ref "JUMPER") (pin "1") (pinfunction "1_1") (pintype "passive"))
      (node (ref "U5") (pin "P$10") (pinfunction "VBAT2_P$10") (pintype "bidirectional"))
      (node (ref "U5") (pin "P$9") (pinfunction "VBAT1_P$9") (pintype "bidirectional"))
    )
    (net (code "3") (name "/CTS") (class "Default")
      (node (ref "U$8") (pin "RTS") (pinfunction "RTS_RTS") (pintype "bidirectional"))
      (node (ref "U10") (pin "11") (pinfunction "PD7(AIN1)_11") (pintype "bidirectional"))
    )
    (net (code "4") (name "/CURRENT_CH1") (class "Default")
      (node (ref "C51") (pin "2") (pinfunction "2_2") (pintype "passive"))
      (node (ref "R35") (pin "2") (pinfunction "2_2") (pintype "passive"))
      (node (ref "U$12") (pin "P3") (pinfunction "P$3_P3") (pintype "bidirectional"))
      (node (ref "U$6") (pin "2") (pinfunction "-IN_A_2") (pintype "bidirectional"))
    )
    (net (code "5") (name "/CURRENT_CH2") (class "Default")
      (node (ref "C52") (pin "1") (pinfunction "1_1") (pintype "passive"))
      (node (ref "R36") (pin "1") (pinfunction "1_1") (pintype "passive"))
      (node (ref "U$12") (pin "P5") (pinfunction "P$5_P5") (pintype "bidirectional"))
      (node (ref "U$6") (pin "6") (pinfunction "-IN_B_6") (pintype "bidirectional"))
    )
    (net (code "6") (name "/N$66") (class "Default")
      (node (ref "U$1") (pin "4") (pinfunction "IN+_4") (pintype "bidirectional"))
      (node (ref "U$12") (pin "P6") (pinfunction "P$6_P6") (pintype "bidirectional"))
    )
    (net (code "7") (name "/RTS") (class "Default")
      (node (ref "U$8") (pin "CTS") (pinfunction "CTS_CTS") (pintype "bidirectional"))
      (node (ref "U10") (pin "10") (pinfunction "PD6(AIN0)_10") (pintype "bidirectional"))
    )
    (net (code "8") (name "/TEMP_PIN2") (class "Default")
      (node (ref "R6") (pin "1") (pinfunction "1_1") (pintype "passive"))
      (node (ref "U$12") (pin "P2") (pinfunction "P$2_P2") (pintype "bidirectional"))
      (node (ref "U10") (pin "22") (pinfunction "ADC7_22") (pintype "bidirectional"))
    )
    (net (code "9") (name "/VOLTAGE_CH2") (class "Default")
      (node (ref "U$12") (pin "P7") (pinfunction "P$7_P7") (pintype "bidirectional"))
      (node (ref "U$2") (pin "4") (pinfunction "IN+_4") (pintype "bidirectional"))
    )
    (net (code "10") (name "/VOLTAGE_CH3") (class "Default")
      (node (ref "U$12") (pin "P9") (pinfunction "P$9_P9") (pintype "bidirectional"))
      (node (ref "U$3") (pin "4") (pinfunction "IN+_4") (pintype "bidirectional"))
    )
    (net (code "11") (name "/VOLTAGE_CH4") (class "Default")
      (node (ref "U$12") (pin "P10") (pinfunction "P$10_P10") (pintype "bidirectional"))
      (node (ref "U$4") (pin "4") (pinfunction "IN+_4") (pintype "bidirectional"))
    )
    (net (code "12") (name "/VOLTAGE_REF") (class "Default")
      (node (ref "R5") (pin "2") (pinfunction "2_2") (pintype "passive"))
      (node (ref "U$1") (pin "1") (pinfunction "IN-_1") (pintype "bidirectional"))
      (node (ref "U$12") (pin "P8") (pinfunction "P$8_P8") (pintype "bidirectional"))
      (node (ref "U$2") (pin "1") (pinfunction "IN-_1") (pintype "bidirectional"))
      (node (ref "U$3") (pin "1") (pinfunction "IN-_1") (pintype "bidirectional"))
      (node (ref "U$4") (pin "1") (pinfunction "IN-_1") (pintype "bidirectional"))
    )
    (net (code "13") (name "5.0V") (class "Default")
      (node (ref "C49") (pin "1") (pinfunction "P$1_1") (pintype "passive"))
      (node (ref "LED1") (pin "A") (pinfunction "A_A") (pintype "passive"))
      (node (ref "LED2") (pin "A") (pinfunction "A_A") (pintype "passive"))
      (node (ref "LED3") (pin "A") (pinfunction "A_A") (pintype "passive"))
      (node (ref "U$10") (pin "5") (pinfunction "USB5_5") (pintype "bidirectional"))
      (node (ref "U5") (pin "P$1") (pinfunction "VDD1_P$1") (pintype "bidirectional"))
      (node (ref "U5") (pin "P$2") (pinfunction "VDD2_P$2") (pintype "bidirectional"))
    )
    (net (code "14") (name "CH1_LPF1_OUT") (class "Default")
      (node (ref "C6") (pin "2") (pinfunction "2_2") (pintype "passive"))
      (node (ref "C7") (pin "2") (pinfunction "2_2") (pintype "passive"))
      (node (ref "R10") (pin "1") (pinfunction "1_1") (pintype "passive"))
      (node (ref "U3") (pin "1") (pinfunction "OUT_A_1") (pintype "output"))
      (node (ref "U3") (pin "2") (pinfunction "-IN_A_2") (pintype "input"))
    )
    (net (code "15") (name "CH1_LPF2_OUT") (class "Default")
      (node (ref "C11") (pin "2") (pinfunction "2_2") (pintype "passive"))
      (node (ref "C12") (pin "2") (pinfunction "2_2") (pintype "passive"))
      (node (ref "U10") (pin "25") (pinfunction "PC2(ADC2)_25") (pintype "bidirectional"))
      (node (ref "U3") (pin "15") (pinfunction "-IN_D_15") (pintype "input"))
      (node (ref "U3") (pin "16") (pinfunction "OUT_D_16") (pintype "output"))
    )
    (net (code "16") (name "CH2_LPF1_OUT") (class "Default")
      (node (ref "C16") (pin "2") (pinfunction "2_2") (pintype "passive"))
      (node (ref "C17") (pin "2") (pinfunction "2_2") (pintype "passive"))
      (node (ref "R23") (pin "1") (pinfunction "1_1") (pintype "passive"))
      (node (ref "U3") (pin "6") (pinfunction "-IN_B_6") (pintype "input"))
      (node (ref "U3") (pin "7") (pinfunction "OUT_B_7") (pintype "output"))
    )
    (net (code "17") (name "CH2_LPF2_OUT") (class "Default")
      (node (ref "C19") (pin "2") (pinfunction "2_2") (pintype "passive"))
      (node (ref "C20") (pin "2") (pinfunction "2_2") (pintype "passive"))
      (node (ref "U10") (pin "26") (pinfunction "PC3(ADC3)_26") (pintype "bidirectional"))
      (node (ref "U3") (pin "10") (pinfunction "OUT_C_10") (pintype "output"))
      (node (ref "U3") (pin "11") (pinfunction "-IN_C_11") (pintype "input"))
    )
    (net (code "18") (name "CH3_LPF1_OUT") (class "Default")
      (node (ref "C2") (pin "2") (pinfunction "2_2") (pintype "passive"))
      (node (ref "C3") (pin "2") (pinfunction "2_2") (pintype "passive"))
      (node (ref "R17") (pin "1") (pinfunction "1_1") (pintype "passive"))
      (node (ref "U2") (pin "1") (pinfunction "OUT_A_1") (pintype "output"))
      (node (ref "U2") (pin "2") (pinfunction "-IN_A_2") (pintype "input"))
    )
    (net (code "19") (name "CH3_LPF2_OUT") (class "Default")
      (node (ref "C21") (pin "2") (pinfunction "2_2") (pintype "passive"))
      (node (ref "C22") (pin "2") (pinfunction "2_2") (pintype "passive"))
      (node (ref "U10") (pin "27") (pinfunction "PC4(ADC4/SDA)_27") (pintype "bidirectional"))
      (node (ref "U2") (pin "15") (pinfunction "-IN_D_15") (pintype "input"))
      (node (ref "U2") (pin "16") (pinfunction "OUT_D_16") (pintype "output"))
    )
    (net (code "20") (name "CH4_LPF1_OUT") (class "Default")
      (node (ref "C24") (pin "2") (pinfunction "2_2") (pintype "passive"))
      (node (ref "C25") (pin "2") (pinfunction "2_2") (pintype "passive"))
      (node (ref "R19") (pin "1") (pinfunction "1_1") (pintype "passive"))
      (node (ref "U2") (pin "6") (pinfunction "-IN_B_6") (pintype "input"))
      (node (ref "U2") (pin "7") (pinfunction "OUT_B_7") (pintype "output"))
    )
    (net (code "21") (name "CH4_LPF2_OUT") (class "Default")
      (node (ref "C27") (pin "2") (pinfunction "2_2") (pintype "passive"))
      (node (ref "C28") (pin "2") (pinfunction "2_2") (pintype "passive"))
      (node (ref "U10") (pin "28") (pinfunction "PC5(ADC5/SCL)_28") (pintype "bidirectional"))
      (node (ref "U2") (pin "10") (pinfunction "OUT_C_10") (pintype "output"))
      (node (ref "U2") (pin "11") (pinfunction "-IN_C_11") (pintype "input"))
    )
    (net (code "22") (name "CURRENT_CH1_LPF1_OUT") (class "Default")
      (node (ref "C44") (pin "2") (pinfunction "2_2") (pintype "passive"))
      (node (ref "C45") (pin "2") (pinfunction "2_2") (pintype "passive"))
      (node (ref "R33") (pin "1") (pinfunction "1_1") (pintype "passive"))
      (node (ref "U4") (pin "6") (pinfunction "-IN_B_6") (pintype "input"))
      (node (ref "U4") (pin "7") (pinfunction "OUT_B_7") (pintype "output"))
    )
    (net (code "23") (name "CURRENT_CH1_LPF2_OUT") (class "Default")
      (node (ref "C47") (pin "2") (pinfunction "2_2") (pintype "passive"))
      (node (ref "C48") (pin "2") (pinfunction "2_2") (pintype "passive"))
      (node (ref "U10") (pin "24") (pinfunction "PC1(ADC1)_24") (pintype "bidirectional"))
      (node (ref "U4") (pin "10") (pinfunction "OUT_C_10") (pintype "output"))
      (node (ref "U4") (pin "11") (pinfunction "-IN_C_11") (pintype "input"))
    )
    (net (code "24") (name "CURRENT_CH2_LPF1_OUT") (class "Default")
      (node (ref "C35") (pin "2") (pinfunction "2_2") (pintype "passive"))
      (node (ref "C37") (pin "2") (pinfunction "2_2") (pintype "passive"))
      (node (ref "R31") (pin "1") (pinfunction "1_1") (pintype "passive"))
      (node (ref "U4") (pin "1") (pinfunction "OUT_A_1") (pintype "output"))
      (node (ref "U4") (pin "2") (pinfunction "-IN_A_2") (pintype "input"))
    )
    (net (code "25") (name "CURRENT_CH2_LPF2_OUT") (class "Default")
      (node (ref "C41") (pin "2") (pinfunction "2_2") (pintype "passive"))
      (node (ref "C42") (pin "2") (pinfunction "2_2") (pintype "passive"))
      (node (ref "U10") (pin "23") (pinfunction "PC0(ADC0)_23") (pintype "bidirectional"))
      (node (ref "U4") (pin "15") (pinfunction "-IN_D_15") (pintype "input"))
      (node (ref "U4") (pin "16") (pinfunction "OUT_D_16") (pintype "output"))
    )
    (net (code "26") (name "DIG_VCC") (class "Default")
      (node (ref "C38") (pin "1") (pinfunction "1_1") (pintype "passive"))
      (node (ref "C69") (pin "1") (pinfunction "1_1") (pintype "passive"))
      (node (ref "J1") (pin "2") (pinfunction "J_2") (pintype "passive"))
      (node (ref "R42") (pin "1") (pinfunction "1_1") (pintype "passive"))
      (node (ref "U$7") (pin "5") (pinfunction "VOUT_5") (pintype "output"))
      (node (ref "U10") (pin "4") (pinfunction "VCC_4") (pintype "bidirectional"))
      (node (ref "U10") (pin "6") (pinfunction "VCC_6") (pintype "bidirectional"))
    )
    (net (code "27") (name "GND") (class "Default")
      (node (ref "BATT_NEG") (pin "TP") (pinfunction "TP_TP") (pintype "input"))
      (node (ref "C1") (pin "2") (pinfunction "2_2") (pintype "passive"))
      (node (ref "C10") (pin "2") (pinfunction "2_2") (pintype "passive"))
      (node (ref "C13") (pin "2") (pinfunction "2_2") (pintype "passive"))
      (node (ref "C14") (pin "2") (pinfunction "2_2") (pintype "passive"))
      (node (ref "C15") (pin "2") (pinfunction "2_2") (pintype "passive"))
      (node (ref "C18") (pin "2") (pinfunction "2_2") (pintype "passive"))
      (node (ref "C23") (pin "2") (pinfunction "2_2") (pintype "passive"))
      (node (ref "C26") (pin "2") (pinfunction "2_2") (pintype "passive"))
      (node (ref "C29") (pin "2") (pinfunction "2_2") (pintype "passive"))
      (node (ref "C30") (pin "2") (pinfunction "2_2") (pintype "passive"))
      (node (ref "C31") (pin "2") (pinfunction "2_2") (pintype "passive"))
      (node (ref "C32") (pin "2") (pinfunction "2_2") (pintype "passive"))
      (node (ref "C33") (pin "2") (pinfunction "2_2") (pintype "passive"))
      (node (ref "C34") (pin "2") (pinfunction "2_2") (pintype "passive"))
      (node (ref "C36") (pin "2") (pinfunction "2_2") (pintype "passive"))
      (node (ref "C38") (pin "2") (pinfunction "2_2") (pintype "passive"))
      (node (ref "C39") (pin "2") (pinfunction "2_2") (pintype "passive"))
      (node (ref "C4") (pin "2") (pinfunction "2_2") (pintype "passive"))
      (node (ref "C40") (pin "2") (pinfunction "2_2") (pintype "passive"))
      (node (ref "C43") (pin "2") (pinfunction "2_2") (pintype "passive"))
      (node (ref "C46") (pin "2") (pinfunction "2_2") (pintype "passive"))
      (node (ref "C49") (pin "2") (pinfunction "P$2_2") (pintype "passive"))
      (node (ref "C5") (pin "2") (pinfunction "2_2") (pintype "passive"))
      (node (ref "C50") (pin "2") (pinfunction "2_2") (pintype "passive"))
      (node (ref "C53") (pin "2") (pinfunction "2_2") (pintype "passive"))
      (node (ref "C54") (pin "2") (pinfunction "2_2") (pintype "passive"))
      (node (ref "C56") (pin "2") (pinfunction "2_2") (pintype "passive"))
      (node (ref "C57") (pin "2") (pinfunction "2_2") (pintype "passive"))
      (node (ref "C58") (pin "2") (pinfunction "2_2") (pintype "passive"))
      (node (ref "C60") (pin "2") (pinfunction "2_2") (pintype "passive"))
      (node (ref "C61") (pin "2") (pinfunction "2_2") (pintype "passive"))
      (node (ref "C62") (pin "2") (pinfunction "2_2") (pintype "passive"))
      (node (ref "C63") (pin "2") (pinfunction "2_2") (pintype "passive"))
      (node (ref "C64") (pin "2") (pinfunction "2_2") (pintype "passive"))
      (node (ref "C65") (pin "2") (pinfunction "2_2") (pintype "passive"))
      (node (ref "C66") (pin "1") (pinfunction "1_1") (pintype "passive"))
      (node (ref "C67") (pin "2") (pinfunction "P$2_2") (pintype "passive"))
      (node (ref "C68") (pin "2") (pinfunction "2_2") (pintype "passive"))
      (node (ref "C69") (pin "2") (pinfunction "2_2") (pintype "passive"))
      (node (ref "C8") (pin "2") (pinfunction "2_2") (pintype "passive"))
      (node (ref "C9") (pin "2") (pinfunction "2_2") (pintype "passive"))
      (node (ref "J1") (pin "6") (pinfunction "J_6") (pintype "passive"))
      (node (ref "Q1") (pin "2") (pinfunction "G2_2") (pintype "power_in"))
      (node (ref "Q1") (pin "4") (pinfunction "G1_4") (pintype "power_in"))
      (node (ref "R25") (pin "1") (pinfunction "1_1") (pintype "passive"))
      (node (ref "R39") (pin "1") (pinfunction "1_1") (pintype "passive"))
      (node (ref "R40") (pin "1") (pinfunction "1_1") (pintype "passive"))
      (node (ref "RT2") (pin "1") (pinfunction "1_1") (pintype "passive"))
      (node (ref "U$1") (pin "5") (pinfunction "VSS_5") (pintype "bidirectional"))
      (node (ref "U$10") (pin "1") (pinfunction "USB1_1") (pintype "bidirectional"))
      (node (ref "U$11") (pin "3") (pinfunction "3_3") (pintype "bidirectional"))
      (node (ref "U$2") (pin "5") (pinfunction "VSS_5") (pintype "bidirectional"))
      (node (ref "U$3") (pin "5") (pinfunction "VSS_5") (pintype "bidirectional"))
      (node (ref "U$4") (pin "5") (pinfunction "VSS_5") (pintype "bidirectional"))
      (node (ref "U$5") (pin "2") (pinfunction "GND_2") (pintype "passive"))
      (node (ref "U$6") (pin "4") (pinfunction "V-_4") (pintype "bidirectional"))
      (node (ref "U$7") (pin "2") (pinfunction "GND_2") (pintype "passive"))
      (node (ref "U$8") (pin "GND") (pinfunction "GND_GND") (pintype "bidirectional"))
      (node (ref "U$9") (pin "2") (pinfunction "GND_2") (pintype "bidirectional"))
      (node (ref "U1") (pin "2") (pinfunction "GND_2") (pintype "passive"))
      (node (ref "U10") (pin "21") (pinfunction "AGND_21") (pintype "bidirectional"))
      (node (ref "U10") (pin "3") (pinfunction "GND_3") (pintype "bidirectional"))
      (node (ref "U10") (pin "5") (pinfunction "GND_5") (pintype "bidirectional"))
      (node (ref "U15") (pin "2") (pinfunction "COMM_2") (pintype "bidirectional"))
      (node (ref "U2") (pin "13") (pinfunction "V-_13") (pintype "power_in"))
      (node (ref "U3") (pin "13") (pinfunction "V-_13") (pintype "power_in"))
      (node (ref "U4") (pin "13") (pinfunction "V-_13") (pintype "power_in"))
      (node (ref "U5") (pin "P$5") (pinfunction "GND_P$5") (pintype "bidirectional"))
    )
    (net (code "28") (name "Net-(C2-Pad1)") (class "Default")
      (node (ref "C2") (pin "1") (pinfunction "1_1") (pintype "passive"))
      (node (ref "C3") (pin "1") (pinfunction "1_1") (pintype "passive"))
      (node (ref "R12") (pin "1") (pinfunction "1_1") (pintype "passive"))
      (node (ref "R9") (pin "2") (pinfunction "2_2") (pintype "passive"))
    )
    (net (code "29") (name "Net-(C6-Pad1)") (class "Default")
      (node (ref "C6") (pin "1") (pinfunction "1_1") (pintype "passive"))
      (node (ref "C7") (pin "1") (pinfunction "1_1") (pintype "passive"))
      (node (ref "R13") (pin "2") (pinfunction "2_2") (pintype "passive"))
      (node (ref "R14") (pin "1") (pinfunction "1_1") (pintype "passive"))
    )
    (net (code "30") (name "Net-(C11-Pad1)") (class "Default")
      (node (ref "C11") (pin "1") (pinfunction "1_1") (pintype "passive"))
      (node (ref "C12") (pin "1") (pinfunction "1_1") (pintype "passive"))
      (node (ref "R10") (pin "2") (pinfunction "2_2") (pintype "passive"))
      (node (ref "R11") (pin "1") (pinfunction "1_1") (pintype "passive"))
    )
    (net (code "31") (name "Net-(C16-Pad1)") (class "Default")
      (node (ref "C16") (pin "1") (pinfunction "1_1") (pintype "passive"))
      (node (ref "C17") (pin "1") (pinfunction "1_1") (pintype "passive"))
      (node (ref "R20") (pin "2") (pinfunction "2_2") (pintype "passive"))
      (node (ref "R21") (pin "1") (pinfunction "1_1") (pintype "passive"))
    )
    (net (code "32") (name "Net-(C19-Pad1)") (class "Default")
      (node (ref "C19") (pin "1") (pinfunction "1_1") (pintype "passive"))
      (node (ref "C20") (pin "1") (pinfunction "1_1") (pintype "passive"))
      (node (ref "R23") (pin "2") (pinfunction "2_2") (pintype "passive"))
      (node (ref "R24") (pin "1") (pinfunction "1_1") (pintype "passive"))
    )
    (net (code "33") (name "Net-(C21-Pad1)") (class "Default")
      (node (ref "C21") (pin "1") (pinfunction "1_1") (pintype "passive"))
      (node (ref "C22") (pin "1") (pinfunction "1_1") (pintype "passive"))
      (node (ref "R17") (pin "2") (pinfunction "2_2") (pintype "passive"))
      (node (ref "R18") (pin "1") (pinfunction "1_1") (pintype "passive"))
    )
    (net (code "34") (name "Net-(C24-Pad1)") (class "Default")
      (node (ref "C24") (pin "1") (pinfunction "1_1") (pintype "passive"))
      (node (ref "C25") (pin "1") (pinfunction "1_1") (pintype "passive"))
      (node (ref "R15") (pin "2") (pinfunction "2_2") (pintype "passive"))
      (node (ref "R16") (pin "1") (pinfunction "1_1") (pintype "passive"))
    )
    (net (code "35") (name "Net-(C27-Pad1)") (class "Default")
      (node (ref "C27") (pin "1") (pinfunction "1_1") (pintype "passive"))
      (node (ref "C28") (pin "1") (pinfunction "1_1") (pintype "passive"))
      (node (ref "R19") (pin "2") (pinfunction "2_2") (pintype "passive"))
      (node (ref "R22") (pin "1") (pinfunction "1_1") (pintype "passive"))
    )
    (net (code "36") (name "Net-(C35-Pad1)") (class "Default")
      (node (ref "C35") (pin "1") (pinfunction "1_1") (pintype "passive"))
      (node (ref "C37") (pin "1") (pinfunction "1_1") (pintype "passive"))
      (node (ref "R27") (pin "2") (pinfunction "2_2") (pintype "passive"))
      (node (ref "R28") (pin "1") (pinfunction "1_1") (pintype "passive"))
    )
    (net (code "37") (name "Net-(C41-Pad1)") (class "Default")
      (node (ref "C41") (pin "1") (pinfunction "1_1") (pintype "passive"))
      (node (ref "C42") (pin "1") (pinfunction "1_1") (pintype "passive"))
      (node (ref "R31") (pin "2") (pinfunction "2_2") (pintype "passive"))
      (node (ref "R32") (pin "1") (pinfunction "1_1") (pintype "passive"))
    )
    (net (code "38") (name "Net-(C44-Pad1)") (class "Default")
      (node (ref "C44") (pin "1") (pinfunction "1_1") (pintype "passive"))
      (node (ref "C45") (pin "1") (pinfunction "1_1") (pintype "passive"))
      (node (ref "R29") (pin "2") (pinfunction "2_2") (pintype "passive"))
      (node (ref "R30") (pin "1") (pinfunction "1_1") (pintype "passive"))
    )
    (net (code "39") (name "Net-(C47-Pad1)") (class "Default")
      (node (ref "C47") (pin "1") (pinfunction "1_1") (pintype "passive"))
      (node (ref "C48") (pin "1") (pinfunction "1_1") (pintype "passive"))
      (node (ref "R33") (pin "2") (pinfunction "2_2") (pintype "passive"))
      (node (ref "R34") (pin "1") (pinfunction "1_1") (pintype "passive"))
    )
    (net (code "40") (name "Net-(J1A-J)") (class "Default")
      (node (ref "J1") (pin "1") (pinfunction "J_1") (pintype "passive"))
      (node (ref "U10") (pin "16") (pinfunction "PB4(MISO)_16") (pintype "bidirectional"))
    )
    (net (code "41") (name "Net-(J1C-J)") (class "Default")
      (node (ref "J1") (pin "3") (pinfunction "J_3") (pintype "passive"))
      (node (ref "U10") (pin "17") (pinfunction "PB5(SCK)_17") (pintype "bidirectional"))
    )
    (net (code "42") (name "Net-(J1D-J)") (class "Default")
      (node (ref "J1") (pin "4") (pinfunction "J_4") (pintype "passive"))
      (node (ref "U10") (pin "15") (pinfunction "PB3(MOSI/OC2)_15") (pintype "bidirectional"))
    )
    (net (code "43") (name "Net-(J1E-J)") (class "Default")
      (node (ref "J1") (pin "5") (pinfunction "J_5") (pintype "passive"))
      (node (ref "R42") (pin "2") (pinfunction "2_2") (pintype "passive"))
      (node (ref "U10") (pin "29") (pinfunction "PC6(/RESET)_29") (pintype "bidirectional"))
    )
    (net (code "44") (name "Net-(LED1-PadC)") (class "Default")
      (node (ref "LED1") (pin "C") (pinfunction "C_C") (pintype "passive"))
      (node (ref "R7") (pin "2") (pinfunction "2_2") (pintype "passive"))
    )
    (net (code "45") (name "Net-(LED2-PadC)") (class "Default")
      (node (ref "LED2") (pin "C") (pinfunction "C_C") (pintype "passive"))
      (node (ref "R8") (pin "2") (pinfunction "2_2") (pintype "passive"))
    )
    (net (code "46") (name "Net-(LED3-PadC)") (class "Default")
      (node (ref "LED3") (pin "C") (pinfunction "C_C") (pintype "passive"))
      (node (ref "R38") (pin "1") (pinfunction "1_1") (pintype "passive"))
    )
    (net (code "47") (name "Net-(Q1-X1)") (class "Default")
      (node (ref "C65") (pin "1") (pinfunction "1_1") (pintype "passive"))
      (node (ref "Q1") (pin "1") (pinfunction "X1_1") (pintype "bidirectional"))
      (node (ref "U10") (pin "7") (pinfunction "PB6(XTAL1/TOSC1)_7") (pintype "bidirectional"))
    )
    (net (code "48") (name "Net-(Q1-X2)") (class "Default")
      (node (ref "C66") (pin "2") (pinfunction "2_2") (pintype "passive"))
      (node (ref "Q1") (pin "3") (pinfunction "X2_3") (pintype "bidirectional"))
      (node (ref "U10") (pin "8") (pinfunction "PB7(XTAL2/TOSC2)_8") (pintype "bidirectional"))
    )
    (net (code "49") (name "Net-(R40-Pad2)") (class "Default")
      (node (ref "R40") (pin "2") (pinfunction "2_2") (pintype "passive"))
      (node (ref "RT1") (pin "2") (pinfunction "2_2") (pintype "passive"))
      (node (ref "RT2") (pin "2") (pinfunction "2_2") (pintype "passive"))
    )
    (net (code "50") (name "Net-(U$1-OUT)") (class "Default")
      (node (ref "R13") (pin "1") (pinfunction "1_1") (pintype "passive"))
      (node (ref "U$1") (pin "7") (pinfunction "OUT_7") (pintype "bidirectional"))
    )
    (net (code "51") (name "Net-(U$1-RG+)") (class "Default")
      (node (ref "R1") (pin "2") (pinfunction "2_2") (pintype "passive"))
      (node (ref "U$1") (pin "2") (pinfunction "RG+_2") (pintype "bidirectional"))
    )
    (net (code "52") (name "Net-(U$1-RG-)") (class "Default")
      (node (ref "R1") (pin "1") (pinfunction "1_1") (pintype "passive"))
      (node (ref "U$1") (pin "3") (pinfunction "RG-_3") (pintype "bidirectional"))
    )
    (net (code "53") (name "Net-(U$2-OUT)") (class "Default")
      (node (ref "R20") (pin "1") (pinfunction "1_1") (pintype "passive"))
      (node (ref "U$2") (pin "7") (pinfunction "OUT_7") (pintype "bidirectional"))
    )
    (net (code "54") (name "Net-(U$2-RG+)") (class "Default")
      (node (ref "R2") (pin "2") (pinfunction "2_2") (pintype "passive"))
      (node (ref "U$2") (pin "2") (pinfunction "RG+_2") (pintype "bidirectional"))
    )
    (net (code "55") (name "Net-(U$2-RG-)") (class "Default")
      (node (ref "R2") (pin "1") (pinfunction "1_1") (pintype "passive"))
      (node (ref "U$2") (pin "3") (pinfunction "RG-_3") (pintype "bidirectional"))
    )
    (net (code "56") (name "Net-(U$3-OUT)") (class "Default")
      (node (ref "R9") (pin "1") (pinfunction "1_1") (pintype "passive"))
      (node (ref "U$3") (pin "7") (pinfunction "OUT_7") (pintype "bidirectional"))
    )
    (net (code "57") (name "Net-(U$3-RG+)") (class "Default")
      (node (ref "R3") (pin "2") (pinfunction "2_2") (pintype "passive"))
      (node (ref "U$3") (pin "2") (pinfunction "RG+_2") (pintype "bidirectional"))
    )
    (net (code "58") (name "Net-(U$3-RG-)") (class "Default")
      (node (ref "R3") (pin "1") (pinfunction "1_1") (pintype "passive"))
      (node (ref "U$3") (pin "3") (pinfunction "RG-_3") (pintype "bidirectional"))
    )
    (net (code "59") (name "Net-(U$4-OUT)") (class "Default")
      (node (ref "R15") (pin "1") (pinfunction "1_1") (pintype "passive"))
      (node (ref "U$4") (pin "7") (pinfunction "OUT_7") (pintype "bidirectional"))
    )
    (net (code "60") (name "Net-(U$4-RG+)") (class "Default")
      (node (ref "R4") (pin "2") (pinfunction "2_2") (pintype "passive"))
      (node (ref "U$4") (pin "2") (pinfunction "RG+_2") (pintype "bidirectional"))
    )
    (net (code "61") (name "Net-(U$4-RG-)") (class "Default")
      (node (ref "R4") (pin "1") (pinfunction "1_1") (pintype "passive"))
      (node (ref "U$4") (pin "3") (pinfunction "RG-_3") (pintype "bidirectional"))
    )
    (net (code "62") (name "Net-(U$5-BYPASS)") (class "Default")
      (node (ref "C4") (pin "1") (pinfunction "1_1") (pintype "passive"))
      (node (ref "U$5") (pin "4") (pinfunction "BYPASS_4") (pintype "input"))
    )
    (net (code "63") (name "Net-(U$5-ON{slash}~{OFF})") (class "Default")
      (node (ref "C32") (pin "1") (pinfunction "1_1") (pintype "passive"))
      (node (ref "C33") (pin "1") (pinfunction "1_1") (pintype "passive"))
      (node (ref "C53") (pin "1") (pinfunction "1_1") (pintype "passive"))
      (node (ref "C55") (pin "2") (pinfunction "2_2") (pintype "passive"))
      (node (ref "D1") (pin "C") (pinfunction "C_C") (pintype "passive"))
      (node (ref "R26") (pin "2") (pinfunction "2_2") (pintype "passive"))
      (node (ref "U$5") (pin "1") (pinfunction "VIN_1") (pintype "power_in"))
      (node (ref "U$5") (pin "3") (pinfunction "ON/~{OFF}_3") (pintype "input"))
      (node (ref "U$7") (pin "1") (pinfunction "VIN_1") (pintype "power_in"))
      (node (ref "U$7") (pin "3") (pinfunction "ON/~{OFF}_3") (pintype "input"))
    )
    (net (code "64") (name "Net-(U$6-OUT_A)") (class "Default")
      (node (ref "C51") (pin "1") (pinfunction "1_1") (pintype "passive"))
      (node (ref "R27") (pin "1") (pinfunction "1_1") (pintype "passive"))
      (node (ref "R35") (pin "1") (pinfunction "1_1") (pintype "passive"))
      (node (ref "U$6") (pin "1") (pinfunction "OUT_A_1") (pintype "bidirectional"))
    )
    (net (code "65") (name "Net-(U$6-OUT_B)") (class "Default")
      (node (ref "C52") (pin "2") (pinfunction "2_2") (pintype "passive"))
      (node (ref "R29") (pin "1") (pinfunction "1_1") (pintype "passive"))
      (node (ref "R36") (pin "2") (pinfunction "2_2") (pintype "passive"))
      (node (ref "U$6") (pin "7") (pinfunction "OUT_B_7") (pintype "bidirectional"))
    )
    (net (code "66") (name "Net-(U$7-BYPASS)") (class "Default")
      (node (ref "C8") (pin "1") (pinfunction "1_1") (pintype "passive"))
      (node (ref "U$7") (pin "4") (pinfunction "BYPASS_4") (pintype "input"))
    )
    (net (code "67") (name "Net-(U$9-FB)") (class "Default")
      (node (ref "C55") (pin "1") (pinfunction "1_1") (pintype "passive"))
      (node (ref "R25") (pin "2") (pinfunction "2_2") (pintype "passive"))
      (node (ref "R26") (pin "1") (pinfunction "1_1") (pintype "passive"))
      (node (ref "U$9") (pin "3") (pinfunction "FB_3") (pintype "bidirectional"))
    )
    (net (code "68") (name "Net-(U$9-SW)") (class "Default")
      (node (ref "D1") (pin "A") (pinfunction "A_A") (pintype "passive"))
      (node (ref "L2") (pin "2") (pinfunction "2_2") (pintype "passive"))
      (node (ref "U$9") (pin "1") (pinfunction "SW_1") (pintype "bidirectional"))
    )
    (net (code "69") (name "Net-(U$11-COMM)") (class "Default")
      (node (ref "U$11") (pin "2") (pinfunction "COMM_2") (pintype "bidirectional"))
      (node (ref "U$9") (pin "4") (pinfunction "SHDN_BAR_4") (pintype "bidirectional"))
      (node (ref "U1") (pin "3") (pinfunction "ON/OFF_3") (pintype "input"))
    )
    (net (code "70") (name "Net-(U1-BYPASS)") (class "Default")
      (node (ref "C57") (pin "1") (pinfunction "1_1") (pintype "passive"))
      (node (ref "U1") (pin "4") (pinfunction "BYPASS_4") (pintype "input"))
    )
    (net (code "71") (name "Net-(U2-+IN_A)") (class "Default")
      (node (ref "C1") (pin "1") (pinfunction "1_1") (pintype "passive"))
      (node (ref "R12") (pin "2") (pinfunction "2_2") (pintype "passive"))
      (node (ref "U2") (pin "3") (pinfunction "+IN_A_3") (pintype "input"))
    )
    (net (code "72") (name "Net-(U2-+IN_B)") (class "Default")
      (node (ref "C23") (pin "1") (pinfunction "1_1") (pintype "passive"))
      (node (ref "R16") (pin "2") (pinfunction "2_2") (pintype "passive"))
      (node (ref "U2") (pin "5") (pinfunction "+IN_B_5") (pintype "input"))
    )
    (net (code "73") (name "Net-(U2-+IN_C)") (class "Default")
      (node (ref "C26") (pin "1") (pinfunction "1_1") (pintype "passive"))
      (node (ref "R22") (pin "2") (pinfunction "2_2") (pintype "passive"))
      (node (ref "U2") (pin "12") (pinfunction "+IN_C_12") (pintype "input"))
    )
    (net (code "74") (name "Net-(U2-+IN_D)") (class "Default")
      (node (ref "C14") (pin "1") (pinfunction "1_1") (pintype "passive"))
      (node (ref "R18") (pin "2") (pinfunction "2_2") (pintype "passive"))
      (node (ref "U2") (pin "14") (pinfunction "+IN_D_14") (pintype "input"))
    )
    (net (code "75") (name "Net-(U3-+IN_A)") (class "Default")
      (node (ref "C5") (pin "1") (pinfunction "1_1") (pintype "passive"))
      (node (ref "R14") (pin "2") (pinfunction "2_2") (pintype "passive"))
      (node (ref "U3") (pin "3") (pinfunction "+IN_A_3") (pintype "input"))
    )
    (net (code "76") (name "Net-(U3-+IN_B)") (class "Default")
      (node (ref "C15") (pin "1") (pinfunction "1_1") (pintype "passive"))
      (node (ref "R21") (pin "2") (pinfunction "2_2") (pintype "passive"))
      (node (ref "U3") (pin "5") (pinfunction "+IN_B_5") (pintype "input"))
    )
    (net (code "77") (name "Net-(U3-+IN_C)") (class "Default")
      (node (ref "C18") (pin "1") (pinfunction "1_1") (pintype "passive"))
      (node (ref "R24") (pin "2") (pinfunction "2_2") (pintype "passive"))
      (node (ref "U3") (pin "12") (pinfunction "+IN_C_12") (pintype "input"))
    )
    (net (code "78") (name "Net-(U3-+IN_D)") (class "Default")
      (node (ref "C10") (pin "1") (pinfunction "1_1") (pintype "passive"))
      (node (ref "R11") (pin "2") (pinfunction "2_2") (pintype "passive"))
      (node (ref "U3") (pin "14") (pinfunction "+IN_D_14") (pintype "input"))
    )
    (net (code "79") (name "Net-(U4-+IN_A)") (class "Default")
      (node (ref "C31") (pin "1") (pinfunction "1_1") (pintype "passive"))
      (node (ref "R28") (pin "2") (pinfunction "2_2") (pintype "passive"))
      (node (ref "U4") (pin "3") (pinfunction "+IN_A_3") (pintype "input"))
    )
    (net (code "80") (name "Net-(U4-+IN_B)") (class "Default")
      (node (ref "C43") (pin "1") (pinfunction "1_1") (pintype "passive"))
      (node (ref "R30") (pin "2") (pinfunction "2_2") (pintype "passive"))
      (node (ref "U4") (pin "5") (pinfunction "+IN_B_5") (pintype "input"))
    )
    (net (code "81") (name "Net-(U4-+IN_C)") (class "Default")
      (node (ref "C46") (pin "1") (pinfunction "1_1") (pintype "passive"))
      (node (ref "R34") (pin "2") (pinfunction "2_2") (pintype "passive"))
      (node (ref "U4") (pin "12") (pinfunction "+IN_C_12") (pintype "input"))
    )
    (net (code "82") (name "Net-(U4-+IN_D)") (class "Default")
      (node (ref "C40") (pin "1") (pinfunction "1_1") (pintype "passive"))
      (node (ref "R32") (pin "2") (pinfunction "2_2") (pintype "passive"))
      (node (ref "U4") (pin "14") (pinfunction "+IN_D_14") (pintype "input"))
    )
    (net (code "83") (name "Net-(U5-PG)") (class "Default")
      (node (ref "R38") (pin "2") (pinfunction "2_2") (pintype "passive"))
      (node (ref "U5") (pin "P$7") (pinfunction "PG_P$7") (pintype "bidirectional"))
    )
    (net (code "84") (name "Net-(U5-PROG)") (class "Default")
      (node (ref "R39") (pin "2") (pinfunction "2_2") (pintype "passive"))
      (node (ref "U5") (pin "P$6") (pinfunction "PROG_P$6") (pintype "bidirectional"))
    )
    (net (code "85") (name "Net-(U5-STAT1)") (class "Default")
      (node (ref "R7") (pin "1") (pinfunction "1_1") (pintype "passive"))
      (node (ref "U5") (pin "P$3") (pinfunction "STAT1_P$3") (pintype "bidirectional"))
    )
    (net (code "86") (name "Net-(U5-STAT2)") (class "Default")
      (node (ref "R8") (pin "1") (pinfunction "1_1") (pintype "passive"))
      (node (ref "U5") (pin "P$4") (pinfunction "STAT2_P$4") (pintype "bidirectional"))
    )
    (net (code "87") (name "Net-(U5-THERM)") (class "Default")
      (node (ref "RT1") (pin "1") (pinfunction "1_1") (pintype "passive"))
      (node (ref "U5") (pin "P$8") (pinfunction "THERM_P$8") (pintype "bidirectional"))
    )
    (net (code "88") (name "Net-(U10-PD0(RXD))") (class "Default")
      (node (ref "U$8") (pin "TXD") (pinfunction "TXD_TXD") (pintype "bidirectional"))
      (node (ref "U10") (pin "30") (pinfunction "PD0(RXD)_30") (pintype "bidirectional"))
    )
    (net (code "89") (name "Net-(U10-PD1(TXD))") (class "Default")
      (node (ref "U$8") (pin "RXD") (pinfunction "RXD_RXD") (pintype "bidirectional"))
      (node (ref "U10") (pin "31") (pinfunction "PD1(TXD)_31") (pintype "bidirectional"))
    )
    (net (code "90") (name "Net-(U15-NOISE)") (class "Default")
      (node (ref "C30") (pin "1") (pinfunction "1_1") (pintype "passive"))
      (node (ref "U15") (pin "8") (pinfunction "NOISE_8") (pintype "bidirectional"))
    )
    (net (code "91") (name "VDDA") (class "Default")
      (node (ref "C13") (pin "1") (pinfunction "1_1") (pintype "passive"))
      (node (ref "C29") (pin "1") (pinfunction "1_1") (pintype "passive"))
      (node (ref "C34") (pin "1") (pinfunction "1_1") (pintype "passive"))
      (node (ref "C39") (pin "1") (pinfunction "1_1") (pintype "passive"))
      (node (ref "C50") (pin "1") (pinfunction "1_1") (pintype "passive"))
      (node (ref "C60") (pin "1") (pinfunction "1_1") (pintype "passive"))
      (node (ref "C62") (pin "1") (pinfunction "1_1") (pintype "passive"))
      (node (ref "C63") (pin "1") (pinfunction "1_1") (pintype "passive"))
      (node (ref "C64") (pin "1") (pinfunction "1_1") (pintype "passive"))
      (node (ref "C68") (pin "1") (pinfunction "1_1") (pintype "passive"))
      (node (ref "C9") (pin "1") (pinfunction "1_1") (pintype "passive"))
      (node (ref "R6") (pin "2") (pinfunction "2_2") (pintype "passive"))
      (node (ref "U$1") (pin "8") (pinfunction "VCC_8") (pintype "bidirectional"))
      (node (ref "U$2") (pin "8") (pinfunction "VCC_8") (pintype "bidirectional"))
      (node (ref "U$3") (pin "8") (pinfunction "VCC_8") (pintype "bidirectional"))
      (node (ref "U$4") (pin "8") (pinfunction "VCC_8") (pintype "bidirectional"))
      (node (ref "U$5") (pin "5") (pinfunction "VOUT_5") (pintype "output"))
      (node (ref "U$6") (pin "8") (pinfunction "V+_8") (pintype "bidirectional"))
      (node (ref "U10") (pin "18") (pinfunction "AVCC_18") (pintype "bidirectional"))
      (node (ref "U15") (pin "3") (pinfunction "IN_3") (pintype "bidirectional"))
      (node (ref "U2") (pin "4") (pinfunction "V+_4") (pintype "power_in"))
      (node (ref "U3") (pin "4") (pinfunction "V+_4") (pintype "power_in"))
      (node (ref "U4") (pin "4") (pinfunction "V+_4") (pintype "power_in"))
    )
    (net (code "92") (name "V_BAT") (class "Default")
      (node (ref "BATT_POS") (pin "TP") (pinfunction "TP_TP") (pintype "input"))
      (node (ref "C54") (pin "1") (pinfunction "1_1") (pintype "passive"))
      (node (ref "C56") (pin "1") (pinfunction "1_1") (pintype "passive"))
      (node (ref "JUMPER") (pin "2") (pinfunction "2_2") (pintype "passive"))
      (node (ref "L2") (pin "1") (pinfunction "1_1") (pintype "passive"))
      (node (ref "U$11") (pin "1") (pinfunction "1_1") (pintype "bidirectional"))
      (node (ref "U$9") (pin "5") (pinfunction "VIN_5") (pintype "bidirectional"))
      (node (ref "U1") (pin "1") (pinfunction "VIN_1") (pintype "power_in"))
    )
    (net (code "93") (name "V_MIDSUPPLY") (class "Default")
      (node (ref "C36") (pin "1") (pinfunction "1_1") (pintype "passive"))
      (node (ref "R5") (pin "1") (pinfunction "1_1") (pintype "passive"))
      (node (ref "U$1") (pin "6") (pinfunction "REF_6") (pintype "bidirectional"))
      (node (ref "U$12") (pin "P1") (pinfunction "P$1_P1") (pintype "bidirectional"))
      (node (ref "U$12") (pin "P4") (pinfunction "P$4_P4") (pintype "bidirectional"))
      (node (ref "U$2") (pin "6") (pinfunction "REF_6") (pintype "bidirectional"))
      (node (ref "U$3") (pin "6") (pinfunction "REF_6") (pintype "bidirectional"))
      (node (ref "U$4") (pin "6") (pinfunction "REF_6") (pintype "bidirectional"))
      (node (ref "U$6") (pin "3") (pinfunction "+IN_A_3") (pintype "bidirectional"))
      (node (ref "U$6") (pin "5") (pinfunction "+IN_B_5") (pintype "bidirectional"))
      (node (ref "U15") (pin "1") (pinfunction "OUT_1") (pintype "bidirectional"))
    )
    (net (code "94") (name "unconnected-(U$8-PadBOOT)") (class "Default")
      (node (ref "U$8") (pin "BOOT") (pinfunction "BOOT_BOOT") (pintype "bidirectional"))
    )
    (net (code "95") (name "unconnected-(U$8-PadGPIO1)") (class "Default")
      (node (ref "U$8") (pin "GPIO1") (pinfunction "GPIO1_GPIO1") (pintype "bidirectional"))
    )
    (net (code "96") (name "unconnected-(U$8-PadGPIO2)") (class "Default")
      (node (ref "U$8") (pin "GPIO2") (pinfunction "GPIO2_GPIO2") (pintype "bidirectional"))
    )
    (net (code "97") (name "unconnected-(U$8-PadGPIO3)") (class "Default")
      (node (ref "U$8") (pin "GPIO3") (pinfunction "GPIO3_GPIO3") (pintype "bidirectional"))
    )
    (net (code "98") (name "unconnected-(U$8-PadGPIO4)") (class "Default")
      (node (ref "U$8") (pin "GPIO4") (pinfunction "GPIO4_GPIO4") (pintype "bidirectional"))
    )
    (net (code "99") (name "unconnected-(U$8-PadGPIO5)") (class "Default")
      (node (ref "U$8") (pin "GPIO5") (pinfunction "GPIO5_GPIO5") (pintype "bidirectional"))
    )
    (net (code "100") (name "unconnected-(U$8-PadGPIO6)") (class "Default")
      (node (ref "U$8") (pin "GPIO6") (pinfunction "GPIO6_GPIO6") (pintype "bidirectional"))
    )
    (net (code "101") (name "unconnected-(U$8-PadGPIO7)") (class "Default")
      (node (ref "U$8") (pin "GPIO7") (pinfunction "GPIO7_GPIO7") (pintype "bidirectional"))
    )
    (net (code "102") (name "unconnected-(U$8-PadLPO)") (class "Default")
      (node (ref "U$8") (pin "LPO") (pinfunction "LPO_LPO") (pintype "bidirectional"))
    )
    (net (code "103") (name "unconnected-(U$8-PadRESET)") (class "Default")
      (node (ref "U$8") (pin "RESET") (pinfunction "RESET_RESET") (pintype "bidirectional"))
    )
    (net (code "104") (name "unconnected-(U$10-USB2-Pad2)") (class "Default")
      (node (ref "U$10") (pin "2") (pinfunction "USB2_2") (pintype "bidirectional"))
    )
    (net (code "105") (name "unconnected-(U$10-USB3-Pad3)") (class "Default")
      (node (ref "U$10") (pin "3") (pinfunction "USB3_3") (pintype "bidirectional"))
    )
    (net (code "106") (name "unconnected-(U$10-USB4-Pad4)") (class "Default")
      (node (ref "U$10") (pin "4") (pinfunction "USB4_4") (pintype "bidirectional"))
    )
    (net (code "107") (name "unconnected-(U2-NC-Pad8)") (class "Default")
      (node (ref "U2") (pin "8") (pinfunction "NC_8") (pintype "no_connect"))
    )
    (net (code "108") (name "unconnected-(U2-NC_2-Pad9)") (class "Default")
      (node (ref "U2") (pin "9") (pinfunction "NC_2_9") (pintype "no_connect"))
    )
    (net (code "109") (name "unconnected-(U3-NC-Pad8)") (class "Default")
      (node (ref "U3") (pin "8") (pinfunction "NC_8") (pintype "no_connect"))
    )
    (net (code "110") (name "unconnected-(U3-NC_2-Pad9)") (class "Default")
      (node (ref "U3") (pin "9") (pinfunction "NC_2_9") (pintype "no_connect"))
    )
    (net (code "111") (name "unconnected-(U4-NC-Pad8)") (class "Default")
      (node (ref "U4") (pin "8") (pinfunction "NC_8") (pintype "no_connect"))
    )
    (net (code "112") (name "unconnected-(U4-NC_2-Pad9)") (class "Default")
      (node (ref "U4") (pin "9") (pinfunction "NC_2_9") (pintype "no_connect"))
    )
    (net (code "113") (name "unconnected-(U10-ADC6-Pad19)") (class "Default")
      (node (ref "U10") (pin "19") (pinfunction "ADC6_19") (pintype "bidirectional"))
    )
    (net (code "114") (name "unconnected-(U10-AREF-Pad20)") (class "Default")
      (node (ref "U10") (pin "20") (pinfunction "AREF_20") (pintype "bidirectional"))
    )
    (net (code "115") (name "unconnected-(U10-PB0(ICP)-Pad12)") (class "Default")
      (node (ref "U10") (pin "12") (pinfunction "PB0(ICP)_12") (pintype "bidirectional"))
    )
    (net (code "116") (name "unconnected-(U10-PB1(OC1A)-Pad13)") (class "Default")
      (node (ref "U10") (pin "13") (pinfunction "PB1(OC1A)_13") (pintype "bidirectional"))
    )
    (net (code "117") (name "unconnected-(U10-PB2(SS{slash}OC1B)-Pad14)") (class "Default")
      (node (ref "U10") (pin "14") (pinfunction "PB2(SS/OC1B)_14") (pintype "bidirectional"))
    )
    (net (code "118") (name "unconnected-(U10-PD2(INT0)-Pad32)") (class "Default")
      (node (ref "U10") (pin "32") (pinfunction "PD2(INT0)_32") (pintype "bidirectional"))
    )
    (net (code "119") (name "unconnected-(U10-PD3(INT1)-Pad1)") (class "Default")
      (node (ref "U10") (pin "1") (pinfunction "PD3(INT1)_1") (pintype "bidirectional"))
    )
    (net (code "120") (name "unconnected-(U10-PD4(XCK{slash}T0)-Pad2)") (class "Default")
      (node (ref "U10") (pin "2") (pinfunction "PD4(XCK/T0)_2") (pintype "bidirectional"))
    )
    (net (code "121") (name "unconnected-(U10-PD5(T1)-Pad9)") (class "Default")
      (node (ref "U10") (pin "9") (pinfunction "PD5(T1)_9") (pintype "bidirectional"))
    )
    (net (code "122") (name "unconnected-(U15-NC-Pad4)") (class "Default")
      (node (ref "U15") (pin "4") (pinfunction "NC_4") (pintype "bidirectional"))
    )
    (net (code "123") (name "unconnected-(U15-NC2-Pad5)") (class "Default")
      (node (ref "U15") (pin "5") (pinfunction "NC2_5") (pintype "bidirectional"))
    )
    (net (code "124") (name "unconnected-(U15-NC3-Pad6)") (class "Default")
      (node (ref "U15") (pin "6") (pinfunction "NC3_6") (pintype "bidirectional"))
    )
    (net (code "125") (name "unconnected-(U15-NC4-Pad7)") (class "Default")
      (node (ref "U15") (pin "7") (pinfunction "NC4_7") (pintype "bidirectional"))
    )
  )
)
